# LEDprotoFix.net
KiCad netlist of a schematic drawn in EAGLE
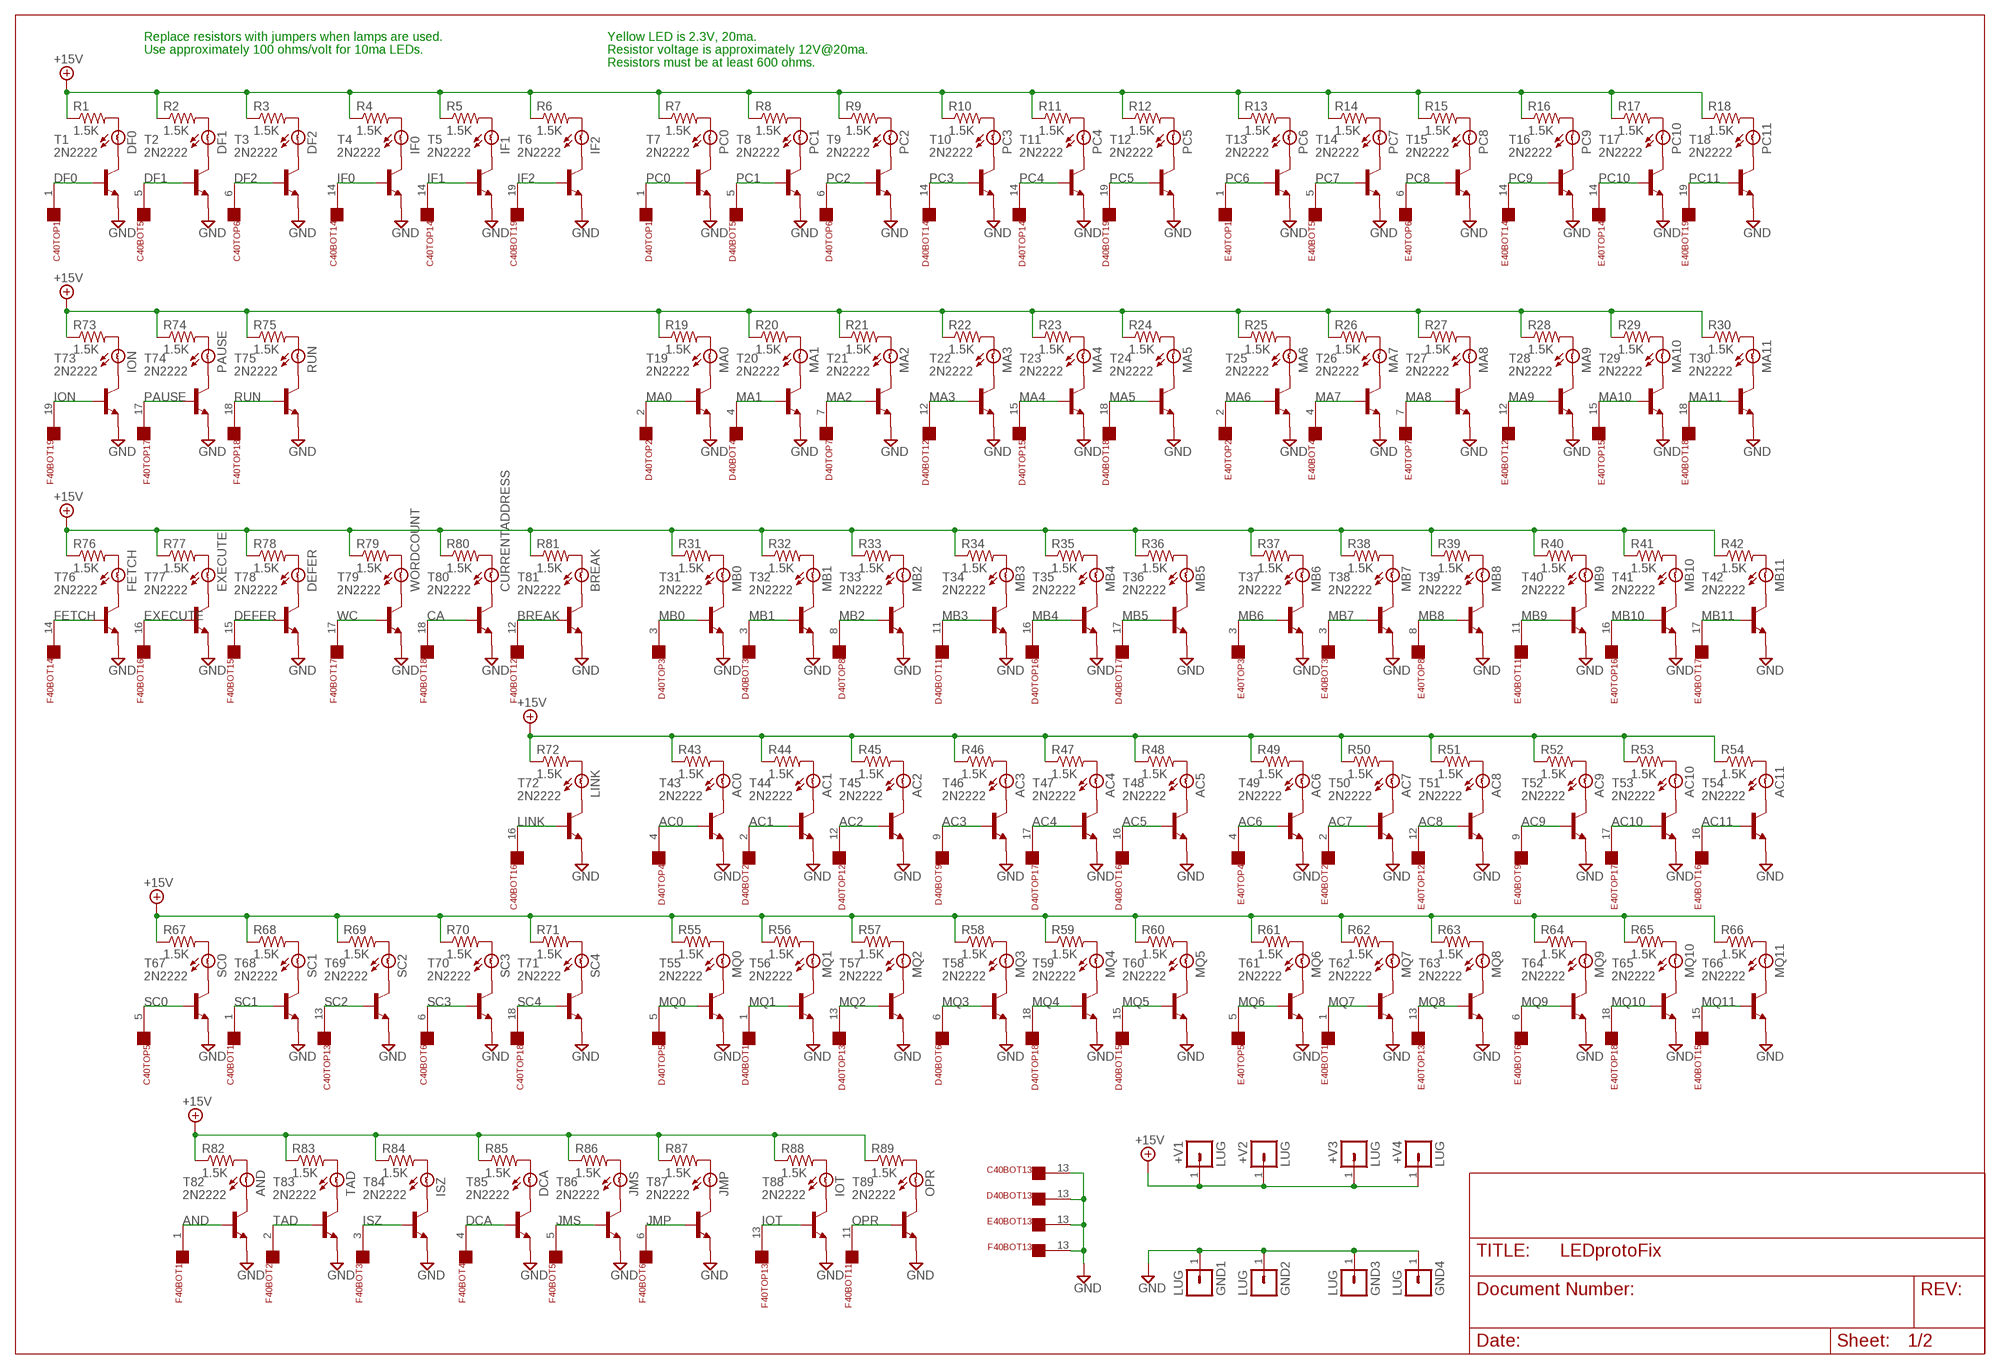
[diagram p0: schematic, sheet 1]
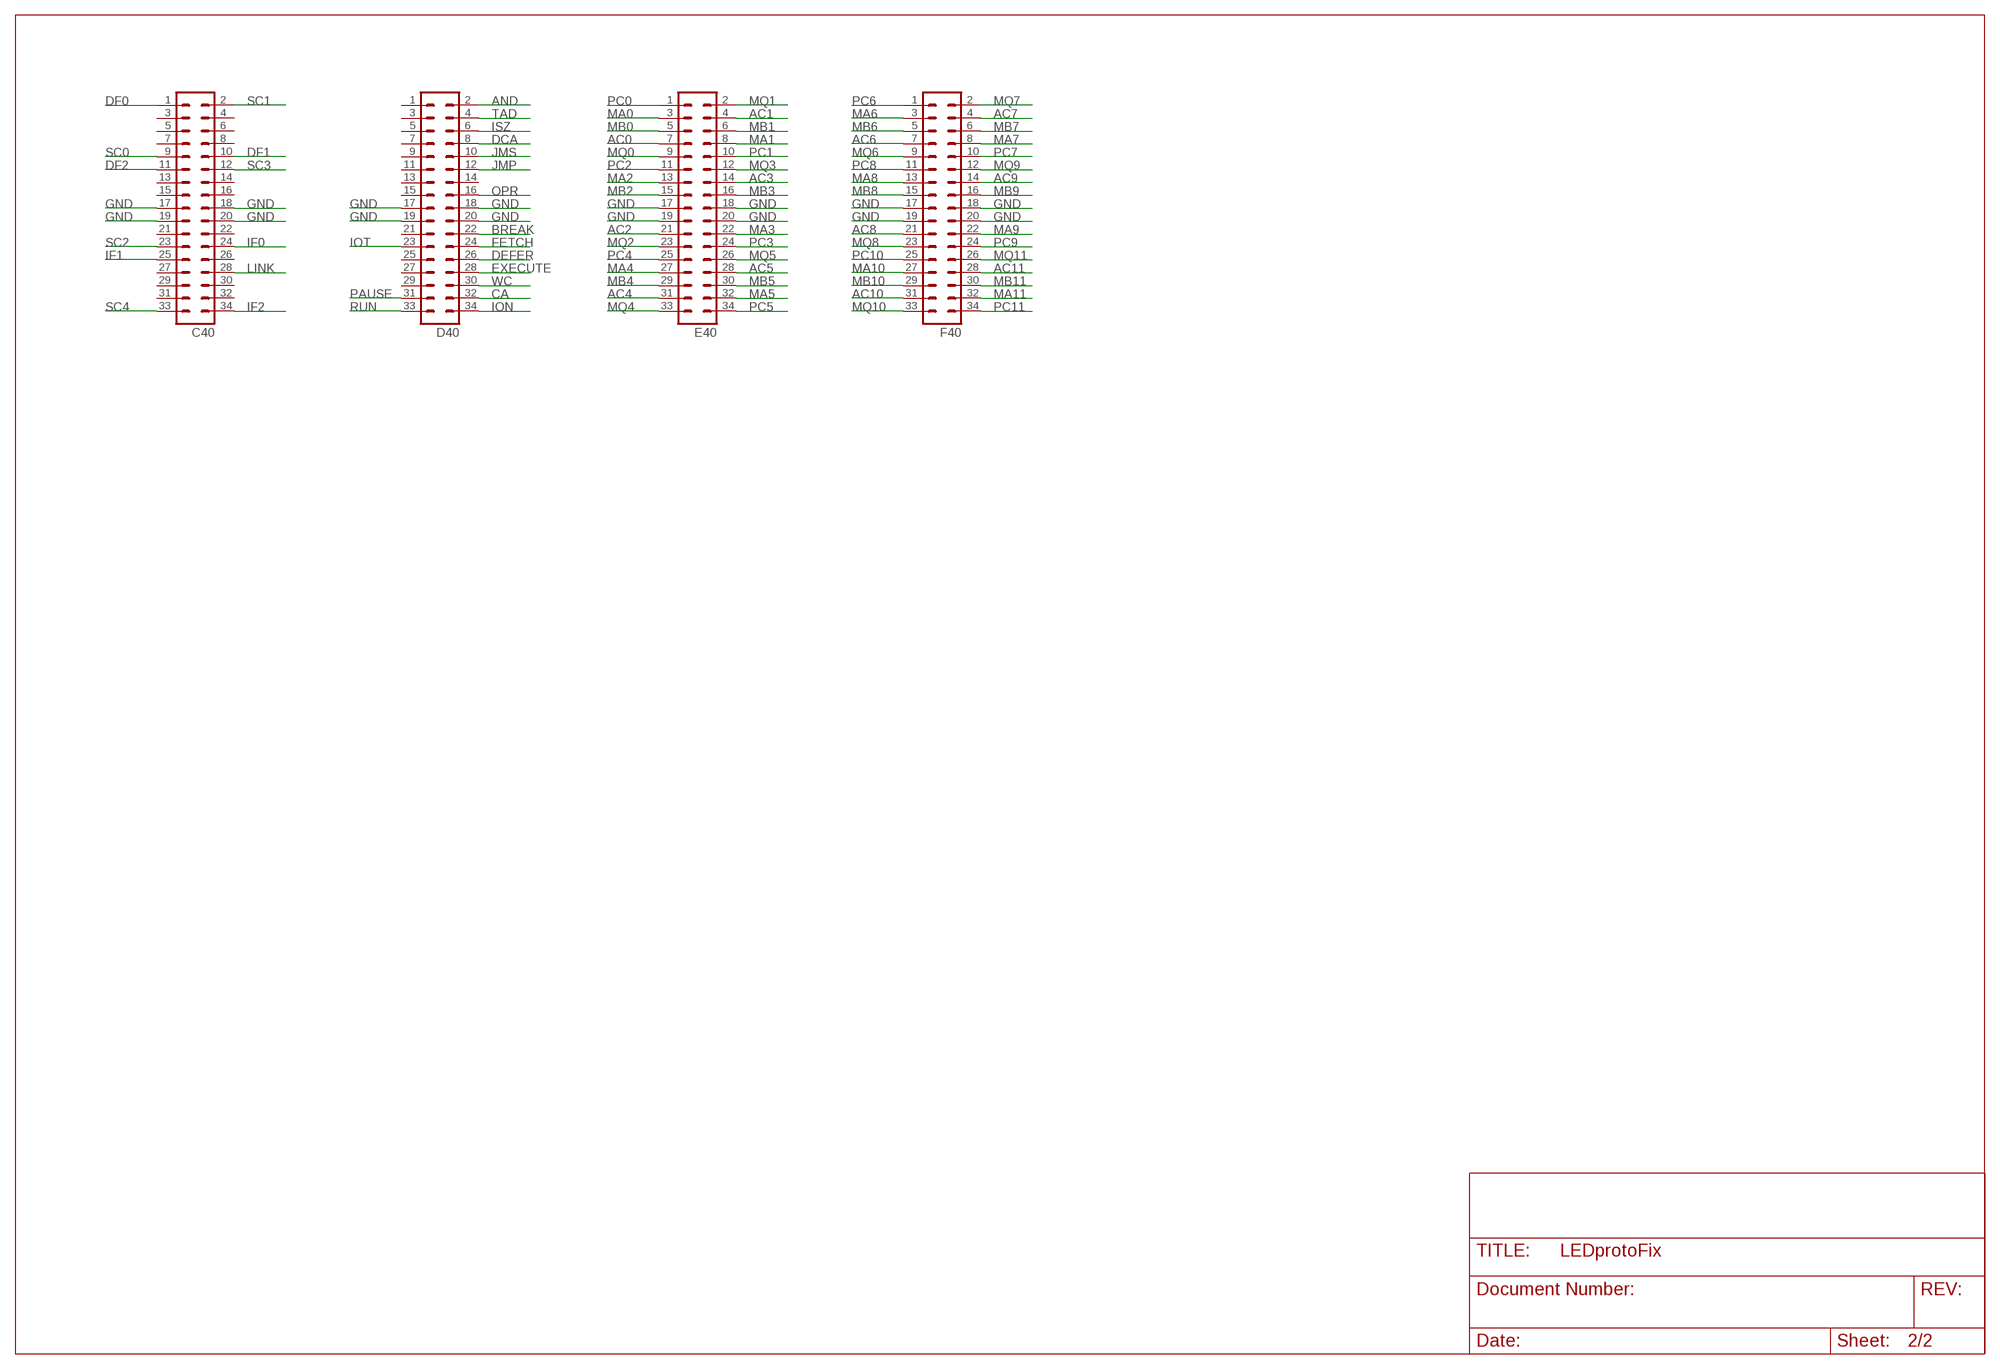
[diagram p1: schematic, sheet 2]

(export (version "E")
  (design (tool "Eeschema 10.0.6"))
  (components
    (comp (ref "+V1")
      (value "LUG")
      (footprint "eagle-import:SPADELUG")
      (libsource (lib "eagle-import") (part "LUG"))
    )
    (comp (ref "+V2")
      (value "LUG")
      (footprint "eagle-import:SPADELUG")
      (libsource (lib "eagle-import") (part "LUG"))
    )
    (comp (ref "+V3")
      (value "LUG")
      (footprint "eagle-import:SPADELUG")
      (libsource (lib "eagle-import") (part "LUG"))
    )
    (comp (ref "+V4")
      (value "LUG")
      (footprint "eagle-import:SPADELUG")
      (libsource (lib "eagle-import") (part "LUG"))
    )
    (comp (ref "AC0")
      (value "BULB")
      (footprint "eagle-import:BULB")
      (libsource (lib "eagle-import") (part "BULB"))
    )
    (comp (ref "AC1")
      (value "BULB")
      (footprint "eagle-import:BULB")
      (libsource (lib "eagle-import") (part "BULB"))
    )
    (comp (ref "AC2")
      (value "BULB")
      (footprint "eagle-import:BULB")
      (libsource (lib "eagle-import") (part "BULB"))
    )
    (comp (ref "AC3")
      (value "BULB")
      (footprint "eagle-import:BULB")
      (libsource (lib "eagle-import") (part "BULB"))
    )
    (comp (ref "AC4")
      (value "BULB")
      (footprint "eagle-import:BULB")
      (libsource (lib "eagle-import") (part "BULB"))
    )
    (comp (ref "AC5")
      (value "BULB")
      (footprint "eagle-import:BULB")
      (libsource (lib "eagle-import") (part "BULB"))
    )
    (comp (ref "AC6")
      (value "BULB")
      (footprint "eagle-import:BULB")
      (libsource (lib "eagle-import") (part "BULB"))
    )
    (comp (ref "AC7")
      (value "BULB")
      (footprint "eagle-import:BULB")
      (libsource (lib "eagle-import") (part "BULB"))
    )
    (comp (ref "AC8")
      (value "BULB")
      (footprint "eagle-import:BULB")
      (libsource (lib "eagle-import") (part "BULB"))
    )
    (comp (ref "AC9")
      (value "BULB")
      (footprint "eagle-import:BULB")
      (libsource (lib "eagle-import") (part "BULB"))
    )
    (comp (ref "AC10")
      (value "BULB")
      (footprint "eagle-import:BULB")
      (libsource (lib "eagle-import") (part "BULB"))
    )
    (comp (ref "AC11")
      (value "BULB")
      (footprint "eagle-import:BULB")
      (libsource (lib "eagle-import") (part "BULB"))
    )
    (comp (ref "AND")
      (value "BULB")
      (footprint "eagle-import:BULB")
      (libsource (lib "eagle-import") (part "BULB"))
    )
    (comp (ref "BREAK")
      (value "BULB")
      (footprint "eagle-import:BULB")
      (libsource (lib "eagle-import") (part "BULB"))
    )
    (comp (ref "C40BOT")
      (value "FLEX19")
      (footprint "eagle-import:FLEX19")
      (libsource (lib "eagle-import") (part "FLEX19"))
    )
    (comp (ref "C40TOP")
      (value "FLEX19")
      (footprint "eagle-import:FLEX19")
      (libsource (lib "eagle-import") (part "FLEX19"))
    )
    (comp (ref "CURRENTADDRESS")
      (value "BULB")
      (footprint "eagle-import:BULB")
      (libsource (lib "eagle-import") (part "BULB"))
    )
    (comp (ref "D40BOT")
      (value "FLEX19")
      (footprint "eagle-import:FLEX19")
      (libsource (lib "eagle-import") (part "FLEX19"))
    )
    (comp (ref "D40TOP")
      (value "FLEX19")
      (footprint "eagle-import:FLEX19")
      (libsource (lib "eagle-import") (part "FLEX19"))
    )
    (comp (ref "DCA")
      (value "BULB")
      (footprint "eagle-import:BULB")
      (libsource (lib "eagle-import") (part "BULB"))
    )
    (comp (ref "DEFER")
      (value "BULB")
      (footprint "eagle-import:BULB")
      (libsource (lib "eagle-import") (part "BULB"))
    )
    (comp (ref "DF0")
      (value "BULB")
      (footprint "eagle-import:BULB")
      (libsource (lib "eagle-import") (part "BULB"))
    )
    (comp (ref "DF1")
      (value "BULB")
      (footprint "eagle-import:BULB")
      (libsource (lib "eagle-import") (part "BULB"))
    )
    (comp (ref "DF2")
      (value "BULB")
      (footprint "eagle-import:BULB")
      (libsource (lib "eagle-import") (part "BULB"))
    )
    (comp (ref "E40BOT")
      (value "FLEX19")
      (footprint "eagle-import:FLEX19")
      (libsource (lib "eagle-import") (part "FLEX19"))
    )
    (comp (ref "E40TOP")
      (value "FLEX19")
      (footprint "eagle-import:FLEX19")
      (libsource (lib "eagle-import") (part "FLEX19"))
    )
    (comp (ref "EXECUTE")
      (value "BULB")
      (footprint "eagle-import:BULB")
      (libsource (lib "eagle-import") (part "BULB"))
    )
    (comp (ref "F40BOT")
      (value "FLEX19")
      (footprint "eagle-import:FLEX19")
      (libsource (lib "eagle-import") (part "FLEX19"))
    )
    (comp (ref "F40TOP")
      (value "FLEX19")
      (footprint "eagle-import:FLEX19")
      (libsource (lib "eagle-import") (part "FLEX19"))
    )
    (comp (ref "FETCH")
      (value "BULB")
      (footprint "eagle-import:BULB")
      (libsource (lib "eagle-import") (part "BULB"))
    )
    (comp (ref "GND1")
      (value "LUG")
      (footprint "eagle-import:SPADELUG")
      (libsource (lib "eagle-import") (part "LUG"))
    )
    (comp (ref "GND2")
      (value "LUG")
      (footprint "eagle-import:SPADELUG")
      (libsource (lib "eagle-import") (part "LUG"))
    )
    (comp (ref "GND3")
      (value "LUG")
      (footprint "eagle-import:SPADELUG")
      (libsource (lib "eagle-import") (part "LUG"))
    )
    (comp (ref "GND4")
      (value "LUG")
      (footprint "eagle-import:SPADELUG")
      (libsource (lib "eagle-import") (part "LUG"))
    )
    (comp (ref "IF0")
      (value "BULB")
      (footprint "eagle-import:BULB")
      (libsource (lib "eagle-import") (part "BULB"))
    )
    (comp (ref "IF1")
      (value "BULB")
      (footprint "eagle-import:BULB")
      (libsource (lib "eagle-import") (part "BULB"))
    )
    (comp (ref "IF2")
      (value "BULB")
      (footprint "eagle-import:BULB")
      (libsource (lib "eagle-import") (part "BULB"))
    )
    (comp (ref "ION")
      (value "BULB")
      (footprint "eagle-import:BULB")
      (libsource (lib "eagle-import") (part "BULB"))
    )
    (comp (ref "IOT")
      (value "BULB")
      (footprint "eagle-import:BULB")
      (libsource (lib "eagle-import") (part "BULB"))
    )
    (comp (ref "ISZ")
      (value "BULB")
      (footprint "eagle-import:BULB")
      (libsource (lib "eagle-import") (part "BULB"))
    )
    (comp (ref "JMP")
      (value "BULB")
      (footprint "eagle-import:BULB")
      (libsource (lib "eagle-import") (part "BULB"))
    )
    (comp (ref "JMS")
      (value "BULB")
      (footprint "eagle-import:BULB")
      (libsource (lib "eagle-import") (part "BULB"))
    )
    (comp (ref "LINK")
      (value "BULB")
      (footprint "eagle-import:BULB")
      (libsource (lib "eagle-import") (part "BULB"))
    )
    (comp (ref "MA0")
      (value "BULB")
      (footprint "eagle-import:BULB")
      (libsource (lib "eagle-import") (part "BULB"))
    )
    (comp (ref "MA1")
      (value "BULB")
      (footprint "eagle-import:BULB")
      (libsource (lib "eagle-import") (part "BULB"))
    )
    (comp (ref "MA2")
      (value "BULB")
      (footprint "eagle-import:BULB")
      (libsource (lib "eagle-import") (part "BULB"))
    )
    (comp (ref "MA3")
      (value "BULB")
      (footprint "eagle-import:BULB")
      (libsource (lib "eagle-import") (part "BULB"))
    )
    (comp (ref "MA4")
      (value "BULB")
      (footprint "eagle-import:BULB")
      (libsource (lib "eagle-import") (part "BULB"))
    )
    (comp (ref "MA5")
      (value "BULB")
      (footprint "eagle-import:BULB")
      (libsource (lib "eagle-import") (part "BULB"))
    )
    (comp (ref "MA6")
      (value "BULB")
      (footprint "eagle-import:BULB")
      (libsource (lib "eagle-import") (part "BULB"))
    )
    (comp (ref "MA7")
      (value "BULB")
      (footprint "eagle-import:BULB")
      (libsource (lib "eagle-import") (part "BULB"))
    )
    (comp (ref "MA8")
      (value "BULB")
      (footprint "eagle-import:BULB")
      (libsource (lib "eagle-import") (part "BULB"))
    )
    (comp (ref "MA9")
      (value "BULB")
      (footprint "eagle-import:BULB")
      (libsource (lib "eagle-import") (part "BULB"))
    )
    (comp (ref "MA10")
      (value "BULB")
      (footprint "eagle-import:BULB")
      (libsource (lib "eagle-import") (part "BULB"))
    )
    (comp (ref "MA11")
      (value "BULB")
      (footprint "eagle-import:BULB")
      (libsource (lib "eagle-import") (part "BULB"))
    )
    (comp (ref "MB0")
      (value "BULB")
      (footprint "eagle-import:BULB")
      (libsource (lib "eagle-import") (part "BULB"))
    )
    (comp (ref "MB1")
      (value "BULB")
      (footprint "eagle-import:BULB")
      (libsource (lib "eagle-import") (part "BULB"))
    )
    (comp (ref "MB2")
      (value "BULB")
      (footprint "eagle-import:BULB")
      (libsource (lib "eagle-import") (part "BULB"))
    )
    (comp (ref "MB3")
      (value "BULB")
      (footprint "eagle-import:BULB")
      (libsource (lib "eagle-import") (part "BULB"))
    )
    (comp (ref "MB4")
      (value "BULB")
      (footprint "eagle-import:BULB")
      (libsource (lib "eagle-import") (part "BULB"))
    )
    (comp (ref "MB5")
      (value "BULB")
      (footprint "eagle-import:BULB")
      (libsource (lib "eagle-import") (part "BULB"))
    )
    (comp (ref "MB6")
      (value "BULB")
      (footprint "eagle-import:BULB")
      (libsource (lib "eagle-import") (part "BULB"))
    )
    (comp (ref "MB7")
      (value "BULB")
      (footprint "eagle-import:BULB")
      (libsource (lib "eagle-import") (part "BULB"))
    )
    (comp (ref "MB8")
      (value "BULB")
      (footprint "eagle-import:BULB")
      (libsource (lib "eagle-import") (part "BULB"))
    )
    (comp (ref "MB9")
      (value "BULB")
      (footprint "eagle-import:BULB")
      (libsource (lib "eagle-import") (part "BULB"))
    )
    (comp (ref "MB10")
      (value "BULB")
      (footprint "eagle-import:BULB")
      (libsource (lib "eagle-import") (part "BULB"))
    )
    (comp (ref "MB11")
      (value "BULB")
      (footprint "eagle-import:BULB")
      (libsource (lib "eagle-import") (part "BULB"))
    )
    (comp (ref "MQ0")
      (value "BULB")
      (footprint "eagle-import:BULB")
      (libsource (lib "eagle-import") (part "BULB"))
    )
    (comp (ref "MQ1")
      (value "BULB")
      (footprint "eagle-import:BULB")
      (libsource (lib "eagle-import") (part "BULB"))
    )
    (comp (ref "MQ2")
      (value "BULB")
      (footprint "eagle-import:BULB")
      (libsource (lib "eagle-import") (part "BULB"))
    )
    (comp (ref "MQ3")
      (value "BULB")
      (footprint "eagle-import:BULB")
      (libsource (lib "eagle-import") (part "BULB"))
    )
    (comp (ref "MQ4")
      (value "BULB")
      (footprint "eagle-import:BULB")
      (libsource (lib "eagle-import") (part "BULB"))
    )
    (comp (ref "MQ5")
      (value "BULB")
      (footprint "eagle-import:BULB")
      (libsource (lib "eagle-import") (part "BULB"))
    )
    (comp (ref "MQ6")
      (value "BULB")
      (footprint "eagle-import:BULB")
      (libsource (lib "eagle-import") (part "BULB"))
    )
    (comp (ref "MQ7")
      (value "BULB")
      (footprint "eagle-import:BULB")
      (libsource (lib "eagle-import") (part "BULB"))
    )
    (comp (ref "MQ8")
      (value "BULB")
      (footprint "eagle-import:BULB")
      (libsource (lib "eagle-import") (part "BULB"))
    )
    (comp (ref "MQ9")
      (value "BULB")
      (footprint "eagle-import:BULB")
      (libsource (lib "eagle-import") (part "BULB"))
    )
    (comp (ref "MQ10")
      (value "BULB")
      (footprint "eagle-import:BULB")
      (libsource (lib "eagle-import") (part "BULB"))
    )
    (comp (ref "MQ11")
      (value "BULB")
      (footprint "eagle-import:BULB")
      (libsource (lib "eagle-import") (part "BULB"))
    )
    (comp (ref "OPR")
      (value "BULB")
      (footprint "eagle-import:BULB")
      (libsource (lib "eagle-import") (part "BULB"))
    )
    (comp (ref "PAUSE")
      (value "BULB")
      (footprint "eagle-import:BULB")
      (libsource (lib "eagle-import") (part "BULB"))
    )
    (comp (ref "PC0")
      (value "BULB")
      (footprint "eagle-import:BULB")
      (libsource (lib "eagle-import") (part "BULB"))
    )
    (comp (ref "PC1")
      (value "BULB")
      (footprint "eagle-import:BULB")
      (libsource (lib "eagle-import") (part "BULB"))
    )
    (comp (ref "PC2")
      (value "BULB")
      (footprint "eagle-import:BULB")
      (libsource (lib "eagle-import") (part "BULB"))
    )
    (comp (ref "PC3")
      (value "BULB")
      (footprint "eagle-import:BULB")
      (libsource (lib "eagle-import") (part "BULB"))
    )
    (comp (ref "PC4")
      (value "BULB")
      (footprint "eagle-import:BULB")
      (libsource (lib "eagle-import") (part "BULB"))
    )
    (comp (ref "PC5")
      (value "BULB")
      (footprint "eagle-import:BULB")
      (libsource (lib "eagle-import") (part "BULB"))
    )
    (comp (ref "PC6")
      (value "BULB")
      (footprint "eagle-import:BULB")
      (libsource (lib "eagle-import") (part "BULB"))
    )
    (comp (ref "PC7")
      (value "BULB")
      (footprint "eagle-import:BULB")
      (libsource (lib "eagle-import") (part "BULB"))
    )
    (comp (ref "PC8")
      (value "BULB")
      (footprint "eagle-import:BULB")
      (libsource (lib "eagle-import") (part "BULB"))
    )
    (comp (ref "PC9")
      (value "BULB")
      (footprint "eagle-import:BULB")
      (libsource (lib "eagle-import") (part "BULB"))
    )
    (comp (ref "PC10")
      (value "BULB")
      (footprint "eagle-import:BULB")
      (libsource (lib "eagle-import") (part "BULB"))
    )
    (comp (ref "PC11")
      (value "BULB")
      (footprint "eagle-import:BULB")
      (libsource (lib "eagle-import") (part "BULB"))
    )
    (comp (ref "R1")
      (value "1.5K")
      (footprint "eagle-import:0207_10")
      (libsource (lib "eagle-import") (part "R-US_0207/10"))
    )
    (comp (ref "R2")
      (value "1.5K")
      (footprint "eagle-import:0207_10")
      (libsource (lib "eagle-import") (part "R-US_0207/10"))
    )
    (comp (ref "R3")
      (value "1.5K")
      (footprint "eagle-import:0207_10")
      (libsource (lib "eagle-import") (part "R-US_0207/10"))
    )
    (comp (ref "R4")
      (value "1.5K")
      (footprint "eagle-import:0207_10")
      (libsource (lib "eagle-import") (part "R-US_0207/10"))
    )
    (comp (ref "R5")
      (value "1.5K")
      (footprint "eagle-import:0207_10")
      (libsource (lib "eagle-import") (part "R-US_0207/10"))
    )
    (comp (ref "R6")
      (value "1.5K")
      (footprint "eagle-import:0207_10")
      (libsource (lib "eagle-import") (part "R-US_0207/10"))
    )
    (comp (ref "R7")
      (value "1.5K")
      (footprint "eagle-import:0207_10")
      (libsource (lib "eagle-import") (part "R-US_0207/10"))
    )
    (comp (ref "R8")
      (value "1.5K")
      (footprint "eagle-import:0207_10")
      (libsource (lib "eagle-import") (part "R-US_0207/10"))
    )
    (comp (ref "R9")
      (value "1.5K")
      (footprint "eagle-import:0207_10")
      (libsource (lib "eagle-import") (part "R-US_0207/10"))
    )
    (comp (ref "R10")
      (value "1.5K")
      (footprint "eagle-import:0207_10")
      (libsource (lib "eagle-import") (part "R-US_0207/10"))
    )
    (comp (ref "R11")
      (value "1.5K")
      (footprint "eagle-import:0207_10")
      (libsource (lib "eagle-import") (part "R-US_0207/10"))
    )
    (comp (ref "R12")
      (value "1.5K")
      (footprint "eagle-import:0207_10")
      (libsource (lib "eagle-import") (part "R-US_0207/10"))
    )
    (comp (ref "R13")
      (value "1.5K")
      (footprint "eagle-import:0207_10")
      (libsource (lib "eagle-import") (part "R-US_0207/10"))
    )
    (comp (ref "R14")
      (value "1.5K")
      (footprint "eagle-import:0207_10")
      (libsource (lib "eagle-import") (part "R-US_0207/10"))
    )
    (comp (ref "R15")
      (value "1.5K")
      (footprint "eagle-import:0207_10")
      (libsource (lib "eagle-import") (part "R-US_0207/10"))
    )
    (comp (ref "R16")
      (value "1.5K")
      (footprint "eagle-import:0207_10")
      (libsource (lib "eagle-import") (part "R-US_0207/10"))
    )
    (comp (ref "R17")
      (value "1.5K")
      (footprint "eagle-import:0207_10")
      (libsource (lib "eagle-import") (part "R-US_0207/10"))
    )
    (comp (ref "R18")
      (value "1.5K")
      (footprint "eagle-import:0207_10")
      (libsource (lib "eagle-import") (part "R-US_0207/10"))
    )
    (comp (ref "R19")
      (value "1.5K")
      (footprint "eagle-import:0207_10")
      (libsource (lib "eagle-import") (part "R-US_0207/10"))
    )
    (comp (ref "R20")
      (value "1.5K")
      (footprint "eagle-import:0207_10")
      (libsource (lib "eagle-import") (part "R-US_0207/10"))
    )
    (comp (ref "R21")
      (value "1.5K")
      (footprint "eagle-import:0207_10")
      (libsource (lib "eagle-import") (part "R-US_0207/10"))
    )
    (comp (ref "R22")
      (value "1.5K")
      (footprint "eagle-import:0207_10")
      (libsource (lib "eagle-import") (part "R-US_0207/10"))
    )
    (comp (ref "R23")
      (value "1.5K")
      (footprint "eagle-import:0207_10")
      (libsource (lib "eagle-import") (part "R-US_0207/10"))
    )
    (comp (ref "R24")
      (value "1.5K")
      (footprint "eagle-import:0207_10")
      (libsource (lib "eagle-import") (part "R-US_0207/10"))
    )
    (comp (ref "R25")
      (value "1.5K")
      (footprint "eagle-import:0207_10")
      (libsource (lib "eagle-import") (part "R-US_0207/10"))
    )
    (comp (ref "R26")
      (value "1.5K")
      (footprint "eagle-import:0207_10")
      (libsource (lib "eagle-import") (part "R-US_0207/10"))
    )
    (comp (ref "R27")
      (value "1.5K")
      (footprint "eagle-import:0207_10")
      (libsource (lib "eagle-import") (part "R-US_0207/10"))
    )
    (comp (ref "R28")
      (value "1.5K")
      (footprint "eagle-import:0207_10")
      (libsource (lib "eagle-import") (part "R-US_0207/10"))
    )
    (comp (ref "R29")
      (value "1.5K")
      (footprint "eagle-import:0207_10")
      (libsource (lib "eagle-import") (part "R-US_0207/10"))
    )
    (comp (ref "R30")
      (value "1.5K")
      (footprint "eagle-import:0207_10")
      (libsource (lib "eagle-import") (part "R-US_0207/10"))
    )
    (comp (ref "R31")
      (value "1.5K")
      (footprint "eagle-import:0207_10")
      (libsource (lib "eagle-import") (part "R-US_0207/10"))
    )
    (comp (ref "R32")
      (value "1.5K")
      (footprint "eagle-import:0207_10")
      (libsource (lib "eagle-import") (part "R-US_0207/10"))
    )
    (comp (ref "R33")
      (value "1.5K")
      (footprint "eagle-import:0207_10")
      (libsource (lib "eagle-import") (part "R-US_0207/10"))
    )
    (comp (ref "R34")
      (value "1.5K")
      (footprint "eagle-import:0207_10")
      (libsource (lib "eagle-import") (part "R-US_0207/10"))
    )
    (comp (ref "R35")
      (value "1.5K")
      (footprint "eagle-import:0207_10")
      (libsource (lib "eagle-import") (part "R-US_0207/10"))
    )
    (comp (ref "R36")
      (value "1.5K")
      (footprint "eagle-import:0207_10")
      (libsource (lib "eagle-import") (part "R-US_0207/10"))
    )
    (comp (ref "R37")
      (value "1.5K")
      (footprint "eagle-import:0207_10")
      (libsource (lib "eagle-import") (part "R-US_0207/10"))
    )
    (comp (ref "R38")
      (value "1.5K")
      (footprint "eagle-import:0207_10")
      (libsource (lib "eagle-import") (part "R-US_0207/10"))
    )
    (comp (ref "R39")
      (value "1.5K")
      (footprint "eagle-import:0207_10")
      (libsource (lib "eagle-import") (part "R-US_0207/10"))
    )
    (comp (ref "R40")
      (value "1.5K")
      (footprint "eagle-import:0207_10")
      (libsource (lib "eagle-import") (part "R-US_0207/10"))
    )
    (comp (ref "R41")
      (value "1.5K")
      (footprint "eagle-import:0207_10")
      (libsource (lib "eagle-import") (part "R-US_0207/10"))
    )
    (comp (ref "R42")
      (value "1.5K")
      (footprint "eagle-import:0207_10")
      (libsource (lib "eagle-import") (part "R-US_0207/10"))
    )
    (comp (ref "R43")
      (value "1.5K")
      (footprint "eagle-import:0207_10")
      (libsource (lib "eagle-import") (part "R-US_0207/10"))
    )
    (comp (ref "R44")
      (value "1.5K")
      (footprint "eagle-import:0207_10")
      (libsource (lib "eagle-import") (part "R-US_0207/10"))
    )
    (comp (ref "R45")
      (value "1.5K")
      (footprint "eagle-import:0207_10")
      (libsource (lib "eagle-import") (part "R-US_0207/10"))
    )
    (comp (ref "R46")
      (value "1.5K")
      (footprint "eagle-import:0207_10")
      (libsource (lib "eagle-import") (part "R-US_0207/10"))
    )
    (comp (ref "R47")
      (value "1.5K")
      (footprint "eagle-import:0207_10")
      (libsource (lib "eagle-import") (part "R-US_0207/10"))
    )
    (comp (ref "R48")
      (value "1.5K")
      (footprint "eagle-import:0207_10")
      (libsource (lib "eagle-import") (part "R-US_0207/10"))
    )
    (comp (ref "R49")
      (value "1.5K")
      (footprint "eagle-import:0207_10")
      (libsource (lib "eagle-import") (part "R-US_0207/10"))
    )
    (comp (ref "R50")
      (value "1.5K")
      (footprint "eagle-import:0207_10")
      (libsource (lib "eagle-import") (part "R-US_0207/10"))
    )
    (comp (ref "R51")
      (value "1.5K")
      (footprint "eagle-import:0207_10")
      (libsource (lib "eagle-import") (part "R-US_0207/10"))
    )
    (comp (ref "R52")
      (value "1.5K")
      (footprint "eagle-import:0207_10")
      (libsource (lib "eagle-import") (part "R-US_0207/10"))
    )
    (comp (ref "R53")
      (value "1.5K")
      (footprint "eagle-import:0207_10")
      (libsource (lib "eagle-import") (part "R-US_0207/10"))
    )
    (comp (ref "R54")
      (value "1.5K")
      (footprint "eagle-import:0207_10")
      (libsource (lib "eagle-import") (part "R-US_0207/10"))
    )
    (comp (ref "R55")
      (value "1.5K")
      (footprint "eagle-import:0207_10")
      (libsource (lib "eagle-import") (part "R-US_0207/10"))
    )
    (comp (ref "R56")
      (value "1.5K")
      (footprint "eagle-import:0207_10")
      (libsource (lib "eagle-import") (part "R-US_0207/10"))
    )
    (comp (ref "R57")
      (value "1.5K")
      (footprint "eagle-import:0207_10")
      (libsource (lib "eagle-import") (part "R-US_0207/10"))
    )
    (comp (ref "R58")
      (value "1.5K")
      (footprint "eagle-import:0207_10")
      (libsource (lib "eagle-import") (part "R-US_0207/10"))
    )
    (comp (ref "R59")
      (value "1.5K")
      (footprint "eagle-import:0207_10")
      (libsource (lib "eagle-import") (part "R-US_0207/10"))
    )
    (comp (ref "R60")
      (value "1.5K")
      (footprint "eagle-import:0207_10")
      (libsource (lib "eagle-import") (part "R-US_0207/10"))
    )
    (comp (ref "R61")
      (value "1.5K")
      (footprint "eagle-import:0207_10")
      (libsource (lib "eagle-import") (part "R-US_0207/10"))
    )
    (comp (ref "R62")
      (value "1.5K")
      (footprint "eagle-import:0207_10")
      (libsource (lib "eagle-import") (part "R-US_0207/10"))
    )
    (comp (ref "R63")
      (value "1.5K")
      (footprint "eagle-import:0207_10")
      (libsource (lib "eagle-import") (part "R-US_0207/10"))
    )
    (comp (ref "R64")
      (value "1.5K")
      (footprint "eagle-import:0207_10")
      (libsource (lib "eagle-import") (part "R-US_0207/10"))
    )
    (comp (ref "R65")
      (value "1.5K")
      (footprint "eagle-import:0207_10")
      (libsource (lib "eagle-import") (part "R-US_0207/10"))
    )
    (comp (ref "R66")
      (value "1.5K")
      (footprint "eagle-import:0207_10")
      (libsource (lib "eagle-import") (part "R-US_0207/10"))
    )
    (comp (ref "R67")
      (value "1.5K")
      (footprint "eagle-import:0207_10")
      (libsource (lib "eagle-import") (part "R-US_0207/10"))
    )
    (comp (ref "R68")
      (value "1.5K")
      (footprint "eagle-import:0207_10")
      (libsource (lib "eagle-import") (part "R-US_0207/10"))
    )
    (comp (ref "R69")
      (value "1.5K")
      (footprint "eagle-import:0207_10")
      (libsource (lib "eagle-import") (part "R-US_0207/10"))
    )
    (comp (ref "R70")
      (value "1.5K")
      (footprint "eagle-import:0207_10")
      (libsource (lib "eagle-import") (part "R-US_0207/10"))
    )
    (comp (ref "R71")
      (value "1.5K")
      (footprint "eagle-import:0207_10")
      (libsource (lib "eagle-import") (part "R-US_0207/10"))
    )
    (comp (ref "R72")
      (value "1.5K")
      (footprint "eagle-import:0207_10")
      (libsource (lib "eagle-import") (part "R-US_0207/10"))
    )
    (comp (ref "R73")
      (value "1.5K")
      (footprint "eagle-import:0207_10")
      (libsource (lib "eagle-import") (part "R-US_0207/10"))
    )
    (comp (ref "R74")
      (value "1.5K")
      (footprint "eagle-import:0207_10")
      (libsource (lib "eagle-import") (part "R-US_0207/10"))
    )
    (comp (ref "R75")
      (value "1.5K")
      (footprint "eagle-import:0207_10")
      (libsource (lib "eagle-import") (part "R-US_0207/10"))
    )
    (comp (ref "R76")
      (value "1.5K")
      (footprint "eagle-import:0207_10")
      (libsource (lib "eagle-import") (part "R-US_0207/10"))
    )
    (comp (ref "R77")
      (value "1.5K")
      (footprint "eagle-import:0207_10")
      (libsource (lib "eagle-import") (part "R-US_0207/10"))
    )
    (comp (ref "R78")
      (value "1.5K")
      (footprint "eagle-import:0207_10")
      (libsource (lib "eagle-import") (part "R-US_0207/10"))
    )
    (comp (ref "R79")
      (value "1.5K")
      (footprint "eagle-import:0207_10")
      (libsource (lib "eagle-import") (part "R-US_0207/10"))
    )
    (comp (ref "R80")
      (value "1.5K")
      (footprint "eagle-import:0207_10")
      (libsource (lib "eagle-import") (part "R-US_0207/10"))
    )
    (comp (ref "R81")
      (value "1.5K")
      (footprint "eagle-import:0207_10")
      (libsource (lib "eagle-import") (part "R-US_0207/10"))
    )
    (comp (ref "R82")
      (value "1.5K")
      (footprint "eagle-import:0207_10")
      (libsource (lib "eagle-import") (part "R-US_0207/10"))
    )
    (comp (ref "R83")
      (value "1.5K")
      (footprint "eagle-import:0207_10")
      (libsource (lib "eagle-import") (part "R-US_0207/10"))
    )
    (comp (ref "R84")
      (value "1.5K")
      (footprint "eagle-import:0207_10")
      (libsource (lib "eagle-import") (part "R-US_0207/10"))
    )
    (comp (ref "R85")
      (value "1.5K")
      (footprint "eagle-import:0207_10")
      (libsource (lib "eagle-import") (part "R-US_0207/10"))
    )
    (comp (ref "R86")
      (value "1.5K")
      (footprint "eagle-import:0207_10")
      (libsource (lib "eagle-import") (part "R-US_0207/10"))
    )
    (comp (ref "R87")
      (value "1.5K")
      (footprint "eagle-import:0207_10")
      (libsource (lib "eagle-import") (part "R-US_0207/10"))
    )
    (comp (ref "R88")
      (value "1.5K")
      (footprint "eagle-import:0207_10")
      (libsource (lib "eagle-import") (part "R-US_0207/10"))
    )
    (comp (ref "R89")
      (value "1.5K")
      (footprint "eagle-import:0207_10")
      (libsource (lib "eagle-import") (part "R-US_0207/10"))
    )
    (comp (ref "RUN")
      (value "BULB")
      (footprint "eagle-import:BULB")
      (libsource (lib "eagle-import") (part "BULB"))
    )
    (comp (ref "SC0")
      (value "BULB")
      (footprint "eagle-import:BULB")
      (libsource (lib "eagle-import") (part "BULB"))
    )
    (comp (ref "SC1")
      (value "BULB")
      (footprint "eagle-import:BULB")
      (libsource (lib "eagle-import") (part "BULB"))
    )
    (comp (ref "SC2")
      (value "BULB")
      (footprint "eagle-import:BULB")
      (libsource (lib "eagle-import") (part "BULB"))
    )
    (comp (ref "SC3")
      (value "BULB")
      (footprint "eagle-import:BULB")
      (libsource (lib "eagle-import") (part "BULB"))
    )
    (comp (ref "SC4")
      (value "BULB")
      (footprint "eagle-import:BULB")
      (libsource (lib "eagle-import") (part "BULB"))
    )
    (comp (ref "T1")
      (value "2N2222")
      (footprint "eagle-import:TO92")
      (libsource (lib "eagle-import") (part "-NPN-TO92"))
    )
    (comp (ref "T2")
      (value "2N2222")
      (footprint "eagle-import:TO92")
      (libsource (lib "eagle-import") (part "-NPN-TO92"))
    )
    (comp (ref "T3")
      (value "2N2222")
      (footprint "eagle-import:TO92")
      (libsource (lib "eagle-import") (part "-NPN-TO92"))
    )
    (comp (ref "T4")
      (value "2N2222")
      (footprint "eagle-import:TO92")
      (libsource (lib "eagle-import") (part "-NPN-TO92"))
    )
    (comp (ref "T5")
      (value "2N2222")
      (footprint "eagle-import:TO92")
      (libsource (lib "eagle-import") (part "-NPN-TO92"))
    )
    (comp (ref "T6")
      (value "2N2222")
      (footprint "eagle-import:TO92")
      (libsource (lib "eagle-import") (part "-NPN-TO92"))
    )
    (comp (ref "T7")
      (value "2N2222")
      (footprint "eagle-import:TO92")
      (libsource (lib "eagle-import") (part "-NPN-TO92"))
    )
    (comp (ref "T8")
      (value "2N2222")
      (footprint "eagle-import:TO92")
      (libsource (lib "eagle-import") (part "-NPN-TO92"))
    )
    (comp (ref "T9")
      (value "2N2222")
      (footprint "eagle-import:TO92")
      (libsource (lib "eagle-import") (part "-NPN-TO92"))
    )
    (comp (ref "T10")
      (value "2N2222")
      (footprint "eagle-import:TO92")
      (libsource (lib "eagle-import") (part "-NPN-TO92"))
    )
    (comp (ref "T11")
      (value "2N2222")
      (footprint "eagle-import:TO92")
      (libsource (lib "eagle-import") (part "-NPN-TO92"))
    )
    (comp (ref "T12")
      (value "2N2222")
      (footprint "eagle-import:TO92")
      (libsource (lib "eagle-import") (part "-NPN-TO92"))
    )
    (comp (ref "T13")
      (value "2N2222")
      (footprint "eagle-import:TO92")
      (libsource (lib "eagle-import") (part "-NPN-TO92"))
    )
    (comp (ref "T14")
      (value "2N2222")
      (footprint "eagle-import:TO92")
      (libsource (lib "eagle-import") (part "-NPN-TO92"))
    )
    (comp (ref "T15")
      (value "2N2222")
      (footprint "eagle-import:TO92")
      (libsource (lib "eagle-import") (part "-NPN-TO92"))
    )
    (comp (ref "T16")
      (value "2N2222")
      (footprint "eagle-import:TO92")
      (libsource (lib "eagle-import") (part "-NPN-TO92"))
    )
    (comp (ref "T17")
      (value "2N2222")
      (footprint "eagle-import:TO92")
      (libsource (lib "eagle-import") (part "-NPN-TO92"))
    )
    (comp (ref "T18")
      (value "2N2222")
      (footprint "eagle-import:TO92")
      (libsource (lib "eagle-import") (part "-NPN-TO92"))
    )
    (comp (ref "T19")
      (value "2N2222")
      (footprint "eagle-import:TO92")
      (libsource (lib "eagle-import") (part "-NPN-TO92"))
    )
    (comp (ref "T20")
      (value "2N2222")
      (footprint "eagle-import:TO92")
      (libsource (lib "eagle-import") (part "-NPN-TO92"))
    )
    (comp (ref "T21")
      (value "2N2222")
      (footprint "eagle-import:TO92")
      (libsource (lib "eagle-import") (part "-NPN-TO92"))
    )
    (comp (ref "T22")
      (value "2N2222")
      (footprint "eagle-import:TO92")
      (libsource (lib "eagle-import") (part "-NPN-TO92"))
    )
    (comp (ref "T23")
      (value "2N2222")
      (footprint "eagle-import:TO92")
      (libsource (lib "eagle-import") (part "-NPN-TO92"))
    )
    (comp (ref "T24")
      (value "2N2222")
      (footprint "eagle-import:TO92")
      (libsource (lib "eagle-import") (part "-NPN-TO92"))
    )
    (comp (ref "T25")
      (value "2N2222")
      (footprint "eagle-import:TO92")
      (libsource (lib "eagle-import") (part "-NPN-TO92"))
    )
    (comp (ref "T26")
      (value "2N2222")
      (footprint "eagle-import:TO92")
      (libsource (lib "eagle-import") (part "-NPN-TO92"))
    )
    (comp (ref "T27")
      (value "2N2222")
      (footprint "eagle-import:TO92")
      (libsource (lib "eagle-import") (part "-NPN-TO92"))
    )
    (comp (ref "T28")
      (value "2N2222")
      (footprint "eagle-import:TO92")
      (libsource (lib "eagle-import") (part "-NPN-TO92"))
    )
    (comp (ref "T29")
      (value "2N2222")
      (footprint "eagle-import:TO92")
      (libsource (lib "eagle-import") (part "-NPN-TO92"))
    )
    (comp (ref "T30")
      (value "2N2222")
      (footprint "eagle-import:TO92")
      (libsource (lib "eagle-import") (part "-NPN-TO92"))
    )
    (comp (ref "T31")
      (value "2N2222")
      (footprint "eagle-import:TO92")
      (libsource (lib "eagle-import") (part "-NPN-TO92"))
    )
    (comp (ref "T32")
      (value "2N2222")
      (footprint "eagle-import:TO92")
      (libsource (lib "eagle-import") (part "-NPN-TO92"))
    )
    (comp (ref "T33")
      (value "2N2222")
      (footprint "eagle-import:TO92")
      (libsource (lib "eagle-import") (part "-NPN-TO92"))
    )
    (comp (ref "T34")
      (value "2N2222")
      (footprint "eagle-import:TO92")
      (libsource (lib "eagle-import") (part "-NPN-TO92"))
    )
    (comp (ref "T35")
      (value "2N2222")
      (footprint "eagle-import:TO92")
      (libsource (lib "eagle-import") (part "-NPN-TO92"))
    )
    (comp (ref "T36")
      (value "2N2222")
      (footprint "eagle-import:TO92")
      (libsource (lib "eagle-import") (part "-NPN-TO92"))
    )
    (comp (ref "T37")
      (value "2N2222")
      (footprint "eagle-import:TO92")
      (libsource (lib "eagle-import") (part "-NPN-TO92"))
    )
    (comp (ref "T38")
      (value "2N2222")
      (footprint "eagle-import:TO92")
      (libsource (lib "eagle-import") (part "-NPN-TO92"))
    )
    (comp (ref "T39")
      (value "2N2222")
      (footprint "eagle-import:TO92")
      (libsource (lib "eagle-import") (part "-NPN-TO92"))
    )
    (comp (ref "T40")
      (value "2N2222")
      (footprint "eagle-import:TO92")
      (libsource (lib "eagle-import") (part "-NPN-TO92"))
    )
    (comp (ref "T41")
      (value "2N2222")
      (footprint "eagle-import:TO92")
      (libsource (lib "eagle-import") (part "-NPN-TO92"))
    )
    (comp (ref "T42")
      (value "2N2222")
      (footprint "eagle-import:TO92")
      (libsource (lib "eagle-import") (part "-NPN-TO92"))
    )
    (comp (ref "T43")
      (value "2N2222")
      (footprint "eagle-import:TO92")
      (libsource (lib "eagle-import") (part "-NPN-TO92"))
    )
    (comp (ref "T44")
      (value "2N2222")
      (footprint "eagle-import:TO92")
      (libsource (lib "eagle-import") (part "-NPN-TO92"))
    )
    (comp (ref "T45")
      (value "2N2222")
      (footprint "eagle-import:TO92")
      (libsource (lib "eagle-import") (part "-NPN-TO92"))
    )
    (comp (ref "T46")
      (value "2N2222")
      (footprint "eagle-import:TO92")
      (libsource (lib "eagle-import") (part "-NPN-TO92"))
    )
    (comp (ref "T47")
      (value "2N2222")
      (footprint "eagle-import:TO92")
      (libsource (lib "eagle-import") (part "-NPN-TO92"))
    )
    (comp (ref "T48")
      (value "2N2222")
      (footprint "eagle-import:TO92")
      (libsource (lib "eagle-import") (part "-NPN-TO92"))
    )
    (comp (ref "T49")
      (value "2N2222")
      (footprint "eagle-import:TO92")
      (libsource (lib "eagle-import") (part "-NPN-TO92"))
    )
    (comp (ref "T50")
      (value "2N2222")
      (footprint "eagle-import:TO92")
      (libsource (lib "eagle-import") (part "-NPN-TO92"))
    )
    (comp (ref "T51")
      (value "2N2222")
      (footprint "eagle-import:TO92")
      (libsource (lib "eagle-import") (part "-NPN-TO92"))
    )
    (comp (ref "T52")
      (value "2N2222")
      (footprint "eagle-import:TO92")
      (libsource (lib "eagle-import") (part "-NPN-TO92"))
    )
    (comp (ref "T53")
      (value "2N2222")
      (footprint "eagle-import:TO92")
      (libsource (lib "eagle-import") (part "-NPN-TO92"))
    )
    (comp (ref "T54")
      (value "2N2222")
      (footprint "eagle-import:TO92")
      (libsource (lib "eagle-import") (part "-NPN-TO92"))
    )
    (comp (ref "T55")
      (value "2N2222")
      (footprint "eagle-import:TO92")
      (libsource (lib "eagle-import") (part "-NPN-TO92"))
    )
    (comp (ref "T56")
      (value "2N2222")
      (footprint "eagle-import:TO92")
      (libsource (lib "eagle-import") (part "-NPN-TO92"))
    )
    (comp (ref "T57")
      (value "2N2222")
      (footprint "eagle-import:TO92")
      (libsource (lib "eagle-import") (part "-NPN-TO92"))
    )
    (comp (ref "T58")
      (value "2N2222")
      (footprint "eagle-import:TO92")
      (libsource (lib "eagle-import") (part "-NPN-TO92"))
    )
    (comp (ref "T59")
      (value "2N2222")
      (footprint "eagle-import:TO92")
      (libsource (lib "eagle-import") (part "-NPN-TO92"))
    )
    (comp (ref "T60")
      (value "2N2222")
      (footprint "eagle-import:TO92")
      (libsource (lib "eagle-import") (part "-NPN-TO92"))
    )
    (comp (ref "T61")
      (value "2N2222")
      (footprint "eagle-import:TO92")
      (libsource (lib "eagle-import") (part "-NPN-TO92"))
    )
    (comp (ref "T62")
      (value "2N2222")
      (footprint "eagle-import:TO92")
      (libsource (lib "eagle-import") (part "-NPN-TO92"))
    )
    (comp (ref "T63")
      (value "2N2222")
      (footprint "eagle-import:TO92")
      (libsource (lib "eagle-import") (part "-NPN-TO92"))
    )
    (comp (ref "T64")
      (value "2N2222")
      (footprint "eagle-import:TO92")
      (libsource (lib "eagle-import") (part "-NPN-TO92"))
    )
    (comp (ref "T65")
      (value "2N2222")
      (footprint "eagle-import:TO92")
      (libsource (lib "eagle-import") (part "-NPN-TO92"))
    )
    (comp (ref "T66")
      (value "2N2222")
      (footprint "eagle-import:TO92")
      (libsource (lib "eagle-import") (part "-NPN-TO92"))
    )
    (comp (ref "T67")
      (value "2N2222")
      (footprint "eagle-import:TO92")
      (libsource (lib "eagle-import") (part "-NPN-TO92"))
    )
    (comp (ref "T68")
      (value "2N2222")
      (footprint "eagle-import:TO92")
      (libsource (lib "eagle-import") (part "-NPN-TO92"))
    )
    (comp (ref "T69")
      (value "2N2222")
      (footprint "eagle-import:TO92")
      (libsource (lib "eagle-import") (part "-NPN-TO92"))
    )
    (comp (ref "T70")
      (value "2N2222")
      (footprint "eagle-import:TO92")
      (libsource (lib "eagle-import") (part "-NPN-TO92"))
    )
    (comp (ref "T71")
      (value "2N2222")
      (footprint "eagle-import:TO92")
      (libsource (lib "eagle-import") (part "-NPN-TO92"))
    )
    (comp (ref "T72")
      (value "2N2222")
      (footprint "eagle-import:TO92")
      (libsource (lib "eagle-import") (part "-NPN-TO92"))
    )
    (comp (ref "T73")
      (value "2N2222")
      (footprint "eagle-import:TO92")
      (libsource (lib "eagle-import") (part "-NPN-TO92"))
    )
    (comp (ref "T74")
      (value "2N2222")
      (footprint "eagle-import:TO92")
      (libsource (lib "eagle-import") (part "-NPN-TO92"))
    )
    (comp (ref "T75")
      (value "2N2222")
      (footprint "eagle-import:TO92")
      (libsource (lib "eagle-import") (part "-NPN-TO92"))
    )
    (comp (ref "T76")
      (value "2N2222")
      (footprint "eagle-import:TO92")
      (libsource (lib "eagle-import") (part "-NPN-TO92"))
    )
    (comp (ref "T77")
      (value "2N2222")
      (footprint "eagle-import:TO92")
      (libsource (lib "eagle-import") (part "-NPN-TO92"))
    )
    (comp (ref "T78")
      (value "2N2222")
      (footprint "eagle-import:TO92")
      (libsource (lib "eagle-import") (part "-NPN-TO92"))
    )
    (comp (ref "T79")
      (value "2N2222")
      (footprint "eagle-import:TO92")
      (libsource (lib "eagle-import") (part "-NPN-TO92"))
    )
    (comp (ref "T80")
      (value "2N2222")
      (footprint "eagle-import:TO92")
      (libsource (lib "eagle-import") (part "-NPN-TO92"))
    )
    (comp (ref "T81")
      (value "2N2222")
      (footprint "eagle-import:TO92")
      (libsource (lib "eagle-import") (part "-NPN-TO92"))
    )
    (comp (ref "T82")
      (value "2N2222")
      (footprint "eagle-import:TO92")
      (libsource (lib "eagle-import") (part "-NPN-TO92"))
    )
    (comp (ref "T83")
      (value "2N2222")
      (footprint "eagle-import:TO92")
      (libsource (lib "eagle-import") (part "-NPN-TO92"))
    )
    (comp (ref "T84")
      (value "2N2222")
      (footprint "eagle-import:TO92")
      (libsource (lib "eagle-import") (part "-NPN-TO92"))
    )
    (comp (ref "T85")
      (value "2N2222")
      (footprint "eagle-import:TO92")
      (libsource (lib "eagle-import") (part "-NPN-TO92"))
    )
    (comp (ref "T86")
      (value "2N2222")
      (footprint "eagle-import:TO92")
      (libsource (lib "eagle-import") (part "-NPN-TO92"))
    )
    (comp (ref "T87")
      (value "2N2222")
      (footprint "eagle-import:TO92")
      (libsource (lib "eagle-import") (part "-NPN-TO92"))
    )
    (comp (ref "T88")
      (value "2N2222")
      (footprint "eagle-import:TO92")
      (libsource (lib "eagle-import") (part "-NPN-TO92"))
    )
    (comp (ref "T89")
      (value "2N2222")
      (footprint "eagle-import:TO92")
      (libsource (lib "eagle-import") (part "-NPN-TO92"))
    )
    (comp (ref "TAD")
      (value "BULB")
      (footprint "eagle-import:BULB")
      (libsource (lib "eagle-import") (part "BULB"))
    )
    (comp (ref "WORDCOUNT")
      (value "BULB")
      (footprint "eagle-import:BULB")
      (libsource (lib "eagle-import") (part "BULB"))
    )
    (comp (ref "C40")
      (value "MA17-2")
      (footprint "eagle-import:MA17-2")
      (libsource (lib "eagle-import") (part "MA17-2"))
    )
    (comp (ref "D40")
      (value "MA17-2")
      (footprint "eagle-import:MA17-2")
      (libsource (lib "eagle-import") (part "MA17-2"))
    )
    (comp (ref "E40")
      (value "MA17-2")
      (footprint "eagle-import:MA17-2")
      (libsource (lib "eagle-import") (part "MA17-2"))
    )
    (comp (ref "F40")
      (value "MA17-2")
      (footprint "eagle-import:MA17-2")
      (libsource (lib "eagle-import") (part "MA17-2"))
    )
  )
  (nets
    (net (code "1") (name "+15V") (class "Default")
      (node (ref "+V1") (pin "1") (pinfunction "1_1") (pintype "passive"))
      (node (ref "+V2") (pin "1") (pinfunction "1_1") (pintype "passive"))
      (node (ref "+V3") (pin "1") (pinfunction "1_1") (pintype "passive"))
      (node (ref "+V4") (pin "1") (pinfunction "1_1") (pintype "passive"))
      (node (ref "R1") (pin "1") (pinfunction "1_1") (pintype "passive"))
      (node (ref "R10") (pin "1") (pinfunction "1_1") (pintype "passive"))
      (node (ref "R11") (pin "1") (pinfunction "1_1") (pintype "passive"))
      (node (ref "R12") (pin "1") (pinfunction "1_1") (pintype "passive"))
      (node (ref "R13") (pin "1") (pinfunction "1_1") (pintype "passive"))
      (node (ref "R14") (pin "1") (pinfunction "1_1") (pintype "passive"))
      (node (ref "R15") (pin "1") (pinfunction "1_1") (pintype "passive"))
      (node (ref "R16") (pin "1") (pinfunction "1_1") (pintype "passive"))
      (node (ref "R17") (pin "1") (pinfunction "1_1") (pintype "passive"))
      (node (ref "R18") (pin "1") (pinfunction "1_1") (pintype "passive"))
      (node (ref "R19") (pin "1") (pinfunction "1_1") (pintype "passive"))
      (node (ref "R2") (pin "1") (pinfunction "1_1") (pintype "passive"))
      (node (ref "R20") (pin "1") (pinfunction "1_1") (pintype "passive"))
      (node (ref "R21") (pin "1") (pinfunction "1_1") (pintype "passive"))
      (node (ref "R22") (pin "1") (pinfunction "1_1") (pintype "passive"))
      (node (ref "R23") (pin "1") (pinfunction "1_1") (pintype "passive"))
      (node (ref "R24") (pin "1") (pinfunction "1_1") (pintype "passive"))
      (node (ref "R25") (pin "1") (pinfunction "1_1") (pintype "passive"))
      (node (ref "R26") (pin "1") (pinfunction "1_1") (pintype "passive"))
      (node (ref "R27") (pin "1") (pinfunction "1_1") (pintype "passive"))
      (node (ref "R28") (pin "1") (pinfunction "1_1") (pintype "passive"))
      (node (ref "R29") (pin "1") (pinfunction "1_1") (pintype "passive"))
      (node (ref "R3") (pin "1") (pinfunction "1_1") (pintype "passive"))
      (node (ref "R30") (pin "1") (pinfunction "1_1") (pintype "passive"))
      (node (ref "R31") (pin "1") (pinfunction "1_1") (pintype "passive"))
      (node (ref "R32") (pin "1") (pinfunction "1_1") (pintype "passive"))
      (node (ref "R33") (pin "1") (pinfunction "1_1") (pintype "passive"))
      (node (ref "R34") (pin "1") (pinfunction "1_1") (pintype "passive"))
      (node (ref "R35") (pin "1") (pinfunction "1_1") (pintype "passive"))
      (node (ref "R36") (pin "1") (pinfunction "1_1") (pintype "passive"))
      (node (ref "R37") (pin "1") (pinfunction "1_1") (pintype "passive"))
      (node (ref "R38") (pin "1") (pinfunction "1_1") (pintype "passive"))
      (node (ref "R39") (pin "1") (pinfunction "1_1") (pintype "passive"))
      (node (ref "R4") (pin "1") (pinfunction "1_1") (pintype "passive"))
      (node (ref "R40") (pin "1") (pinfunction "1_1") (pintype "passive"))
      (node (ref "R41") (pin "1") (pinfunction "1_1") (pintype "passive"))
      (node (ref "R42") (pin "1") (pinfunction "1_1") (pintype "passive"))
      (node (ref "R43") (pin "1") (pinfunction "1_1") (pintype "passive"))
      (node (ref "R44") (pin "1") (pinfunction "1_1") (pintype "passive"))
      (node (ref "R45") (pin "1") (pinfunction "1_1") (pintype "passive"))
      (node (ref "R46") (pin "1") (pinfunction "1_1") (pintype "passive"))
      (node (ref "R47") (pin "1") (pinfunction "1_1") (pintype "passive"))
      (node (ref "R48") (pin "1") (pinfunction "1_1") (pintype "passive"))
      (node (ref "R49") (pin "1") (pinfunction "1_1") (pintype "passive"))
      (node (ref "R5") (pin "1") (pinfunction "1_1") (pintype "passive"))
      (node (ref "R50") (pin "1") (pinfunction "1_1") (pintype "passive"))
      (node (ref "R51") (pin "1") (pinfunction "1_1") (pintype "passive"))
      (node (ref "R52") (pin "1") (pinfunction "1_1") (pintype "passive"))
      (node (ref "R53") (pin "1") (pinfunction "1_1") (pintype "passive"))
      (node (ref "R54") (pin "1") (pinfunction "1_1") (pintype "passive"))
      (node (ref "R55") (pin "1") (pinfunction "1_1") (pintype "passive"))
      (node (ref "R56") (pin "1") (pinfunction "1_1") (pintype "passive"))
      (node (ref "R57") (pin "1") (pinfunction "1_1") (pintype "passive"))
      (node (ref "R58") (pin "1") (pinfunction "1_1") (pintype "passive"))
      (node (ref "R59") (pin "1") (pinfunction "1_1") (pintype "passive"))
      (node (ref "R6") (pin "1") (pinfunction "1_1") (pintype "passive"))
      (node (ref "R60") (pin "1") (pinfunction "1_1") (pintype "passive"))
      (node (ref "R61") (pin "1") (pinfunction "1_1") (pintype "passive"))
      (node (ref "R62") (pin "1") (pinfunction "1_1") (pintype "passive"))
      (node (ref "R63") (pin "1") (pinfunction "1_1") (pintype "passive"))
      (node (ref "R64") (pin "1") (pinfunction "1_1") (pintype "passive"))
      (node (ref "R65") (pin "1") (pinfunction "1_1") (pintype "passive"))
      (node (ref "R66") (pin "1") (pinfunction "1_1") (pintype "passive"))
      (node (ref "R67") (pin "1") (pinfunction "1_1") (pintype "passive"))
      (node (ref "R68") (pin "1") (pinfunction "1_1") (pintype "passive"))
      (node (ref "R69") (pin "1") (pinfunction "1_1") (pintype "passive"))
      (node (ref "R7") (pin "1") (pinfunction "1_1") (pintype "passive"))
      (node (ref "R70") (pin "1") (pinfunction "1_1") (pintype "passive"))
      (node (ref "R71") (pin "1") (pinfunction "1_1") (pintype "passive"))
      (node (ref "R72") (pin "1") (pinfunction "1_1") (pintype "passive"))
      (node (ref "R73") (pin "1") (pinfunction "1_1") (pintype "passive"))
      (node (ref "R74") (pin "1") (pinfunction "1_1") (pintype "passive"))
      (node (ref "R75") (pin "1") (pinfunction "1_1") (pintype "passive"))
      (node (ref "R76") (pin "1") (pinfunction "1_1") (pintype "passive"))
      (node (ref "R77") (pin "1") (pinfunction "1_1") (pintype "passive"))
      (node (ref "R78") (pin "1") (pinfunction "1_1") (pintype "passive"))
      (node (ref "R79") (pin "1") (pinfunction "1_1") (pintype "passive"))
      (node (ref "R8") (pin "1") (pinfunction "1_1") (pintype "passive"))
      (node (ref "R80") (pin "1") (pinfunction "1_1") (pintype "passive"))
      (node (ref "R81") (pin "1") (pinfunction "1_1") (pintype "passive"))
      (node (ref "R82") (pin "1") (pinfunction "1_1") (pintype "passive"))
      (node (ref "R83") (pin "1") (pinfunction "1_1") (pintype "passive"))
      (node (ref "R84") (pin "1") (pinfunction "1_1") (pintype "passive"))
      (node (ref "R85") (pin "1") (pinfunction "1_1") (pintype "passive"))
      (node (ref "R86") (pin "1") (pinfunction "1_1") (pintype "passive"))
      (node (ref "R87") (pin "1") (pinfunction "1_1") (pintype "passive"))
      (node (ref "R88") (pin "1") (pinfunction "1_1") (pintype "passive"))
      (node (ref "R89") (pin "1") (pinfunction "1_1") (pintype "passive"))
      (node (ref "R9") (pin "1") (pinfunction "1_1") (pintype "passive"))
    )
    (net (code "2") (name "AC0") (class "Default")
      (node (ref "D40TOP") (pin "4") (pinfunction "1_4") (pintype "passive"))
      (node (ref "E40") (pin "7") (pinfunction "7_7") (pintype "passive"))
      (node (ref "T43") (pin "2") (pinfunction "B_2") (pintype "passive"))
    )
    (net (code "3") (name "AC1") (class "Default")
      (node (ref "D40BOT") (pin "2") (pinfunction "1_2") (pintype "passive"))
      (node (ref "E40") (pin "4") (pinfunction "4_4") (pintype "passive"))
      (node (ref "T44") (pin "2") (pinfunction "B_2") (pintype "passive"))
    )
    (net (code "4") (name "AC2") (class "Default")
      (node (ref "D40TOP") (pin "12") (pinfunction "1_12") (pintype "passive"))
      (node (ref "E40") (pin "21") (pinfunction "21_21") (pintype "passive"))
      (node (ref "T45") (pin "2") (pinfunction "B_2") (pintype "passive"))
    )
    (net (code "5") (name "AC3") (class "Default")
      (node (ref "D40BOT") (pin "9") (pinfunction "1_9") (pintype "passive"))
      (node (ref "E40") (pin "14") (pinfunction "14_14") (pintype "passive"))
      (node (ref "T46") (pin "2") (pinfunction "B_2") (pintype "passive"))
    )
    (net (code "6") (name "AC4") (class "Default")
      (node (ref "D40TOP") (pin "17") (pinfunction "1_17") (pintype "passive"))
      (node (ref "E40") (pin "31") (pinfunction "31_31") (pintype "passive"))
      (node (ref "T47") (pin "2") (pinfunction "B_2") (pintype "passive"))
    )
    (net (code "7") (name "AC5") (class "Default")
      (node (ref "D40BOT") (pin "16") (pinfunction "1_16") (pintype "passive"))
      (node (ref "E40") (pin "28") (pinfunction "28_28") (pintype "passive"))
      (node (ref "T48") (pin "2") (pinfunction "B_2") (pintype "passive"))
    )
    (net (code "8") (name "AC6") (class "Default")
      (node (ref "E40TOP") (pin "4") (pinfunction "1_4") (pintype "passive"))
      (node (ref "F40") (pin "7") (pinfunction "7_7") (pintype "passive"))
      (node (ref "T49") (pin "2") (pinfunction "B_2") (pintype "passive"))
    )
    (net (code "9") (name "AC7") (class "Default")
      (node (ref "E40BOT") (pin "2") (pinfunction "1_2") (pintype "passive"))
      (node (ref "F40") (pin "4") (pinfunction "4_4") (pintype "passive"))
      (node (ref "T50") (pin "2") (pinfunction "B_2") (pintype "passive"))
    )
    (net (code "10") (name "AC8") (class "Default")
      (node (ref "E40TOP") (pin "12") (pinfunction "1_12") (pintype "passive"))
      (node (ref "F40") (pin "21") (pinfunction "21_21") (pintype "passive"))
      (node (ref "T51") (pin "2") (pinfunction "B_2") (pintype "passive"))
    )
    (net (code "11") (name "AC9") (class "Default")
      (node (ref "E40BOT") (pin "9") (pinfunction "1_9") (pintype "passive"))
      (node (ref "F40") (pin "14") (pinfunction "14_14") (pintype "passive"))
      (node (ref "T52") (pin "2") (pinfunction "B_2") (pintype "passive"))
    )
    (net (code "12") (name "AC10") (class "Default")
      (node (ref "E40TOP") (pin "17") (pinfunction "1_17") (pintype "passive"))
      (node (ref "F40") (pin "31") (pinfunction "31_31") (pintype "passive"))
      (node (ref "T53") (pin "2") (pinfunction "B_2") (pintype "passive"))
    )
    (net (code "13") (name "AC11") (class "Default")
      (node (ref "E40BOT") (pin "16") (pinfunction "1_16") (pintype "passive"))
      (node (ref "F40") (pin "28") (pinfunction "28_28") (pintype "passive"))
      (node (ref "T54") (pin "2") (pinfunction "B_2") (pintype "passive"))
    )
    (net (code "14") (name "AND") (class "Default")
      (node (ref "D40") (pin "2") (pinfunction "2_2") (pintype "passive"))
      (node (ref "F40BOT") (pin "1") (pinfunction "1_1") (pintype "passive"))
      (node (ref "T82") (pin "2") (pinfunction "B_2") (pintype "passive"))
    )
    (net (code "15") (name "BREAK") (class "Default")
      (node (ref "D40") (pin "22") (pinfunction "22_22") (pintype "passive"))
      (node (ref "F40BOT") (pin "12") (pinfunction "1_12") (pintype "passive"))
      (node (ref "T81") (pin "2") (pinfunction "B_2") (pintype "passive"))
    )
    (net (code "16") (name "CA") (class "Default")
      (node (ref "D40") (pin "32") (pinfunction "32_32") (pintype "passive"))
      (node (ref "F40BOT") (pin "18") (pinfunction "1_18") (pintype "passive"))
      (node (ref "T80") (pin "2") (pinfunction "B_2") (pintype "passive"))
    )
    (net (code "17") (name "DCA") (class "Default")
      (node (ref "D40") (pin "8") (pinfunction "8_8") (pintype "passive"))
      (node (ref "F40BOT") (pin "4") (pinfunction "1_4") (pintype "passive"))
      (node (ref "T85") (pin "2") (pinfunction "B_2") (pintype "passive"))
    )
    (net (code "18") (name "DEFER") (class "Default")
      (node (ref "D40") (pin "26") (pinfunction "26_26") (pintype "passive"))
      (node (ref "F40BOT") (pin "15") (pinfunction "1_15") (pintype "passive"))
      (node (ref "T78") (pin "2") (pinfunction "B_2") (pintype "passive"))
    )
    (net (code "19") (name "DF0") (class "Default")
      (node (ref "C40") (pin "1") (pinfunction "1_1") (pintype "passive"))
      (node (ref "C40TOP") (pin "1") (pinfunction "1_1") (pintype "passive"))
      (node (ref "T1") (pin "2") (pinfunction "B_2") (pintype "passive"))
    )
    (net (code "20") (name "DF1") (class "Default")
      (node (ref "C40") (pin "10") (pinfunction "10_10") (pintype "passive"))
      (node (ref "C40BOT") (pin "5") (pinfunction "1_5") (pintype "passive"))
      (node (ref "T2") (pin "2") (pinfunction "B_2") (pintype "passive"))
    )
    (net (code "21") (name "DF2") (class "Default")
      (node (ref "C40") (pin "11") (pinfunction "11_11") (pintype "passive"))
      (node (ref "C40TOP") (pin "6") (pinfunction "1_6") (pintype "passive"))
      (node (ref "T3") (pin "2") (pinfunction "B_2") (pintype "passive"))
    )
    (net (code "22") (name "EXECUTE") (class "Default")
      (node (ref "D40") (pin "28") (pinfunction "28_28") (pintype "passive"))
      (node (ref "F40BOT") (pin "16") (pinfunction "1_16") (pintype "passive"))
      (node (ref "T77") (pin "2") (pinfunction "B_2") (pintype "passive"))
    )
    (net (code "23") (name "FETCH") (class "Default")
      (node (ref "D40") (pin "24") (pinfunction "24_24") (pintype "passive"))
      (node (ref "F40BOT") (pin "14") (pinfunction "1_14") (pintype "passive"))
      (node (ref "T76") (pin "2") (pinfunction "B_2") (pintype "passive"))
    )
    (net (code "24") (name "GND") (class "Default")
      (node (ref "C40") (pin "17") (pinfunction "17_17") (pintype "passive"))
      (node (ref "C40") (pin "18") (pinfunction "18_18") (pintype "passive"))
      (node (ref "C40") (pin "19") (pinfunction "19_19") (pintype "passive"))
      (node (ref "C40") (pin "20") (pinfunction "20_20") (pintype "passive"))
      (node (ref "C40BOT") (pin "13") (pinfunction "1_13") (pintype "passive"))
      (node (ref "D40") (pin "17") (pinfunction "17_17") (pintype "passive"))
      (node (ref "D40") (pin "18") (pinfunction "18_18") (pintype "passive"))
      (node (ref "D40") (pin "19") (pinfunction "19_19") (pintype "passive"))
      (node (ref "D40") (pin "20") (pinfunction "20_20") (pintype "passive"))
      (node (ref "D40BOT") (pin "13") (pinfunction "1_13") (pintype "passive"))
      (node (ref "E40") (pin "17") (pinfunction "17_17") (pintype "passive"))
      (node (ref "E40") (pin "18") (pinfunction "18_18") (pintype "passive"))
      (node (ref "E40") (pin "19") (pinfunction "19_19") (pintype "passive"))
      (node (ref "E40") (pin "20") (pinfunction "20_20") (pintype "passive"))
      (node (ref "E40BOT") (pin "13") (pinfunction "1_13") (pintype "passive"))
      (node (ref "F40") (pin "17") (pinfunction "17_17") (pintype "passive"))
      (node (ref "F40") (pin "18") (pinfunction "18_18") (pintype "passive"))
      (node (ref "F40") (pin "19") (pinfunction "19_19") (pintype "passive"))
      (node (ref "F40") (pin "20") (pinfunction "20_20") (pintype "passive"))
      (node (ref "F40BOT") (pin "13") (pinfunction "1_13") (pintype "passive"))
      (node (ref "GND1") (pin "1") (pinfunction "1_1") (pintype "passive"))
      (node (ref "GND2") (pin "1") (pinfunction "1_1") (pintype "passive"))
      (node (ref "GND3") (pin "1") (pinfunction "1_1") (pintype "passive"))
      (node (ref "GND4") (pin "1") (pinfunction "1_1") (pintype "passive"))
      (node (ref "T1") (pin "1") (pinfunction "E_1") (pintype "passive"))
      (node (ref "T10") (pin "1") (pinfunction "E_1") (pintype "passive"))
      (node (ref "T11") (pin "1") (pinfunction "E_1") (pintype "passive"))
      (node (ref "T12") (pin "1") (pinfunction "E_1") (pintype "passive"))
      (node (ref "T13") (pin "1") (pinfunction "E_1") (pintype "passive"))
      (node (ref "T14") (pin "1") (pinfunction "E_1") (pintype "passive"))
      (node (ref "T15") (pin "1") (pinfunction "E_1") (pintype "passive"))
      (node (ref "T16") (pin "1") (pinfunction "E_1") (pintype "passive"))
      (node (ref "T17") (pin "1") (pinfunction "E_1") (pintype "passive"))
      (node (ref "T18") (pin "1") (pinfunction "E_1") (pintype "passive"))
      (node (ref "T19") (pin "1") (pinfunction "E_1") (pintype "passive"))
      (node (ref "T2") (pin "1") (pinfunction "E_1") (pintype "passive"))
      (node (ref "T20") (pin "1") (pinfunction "E_1") (pintype "passive"))
      (node (ref "T21") (pin "1") (pinfunction "E_1") (pintype "passive"))
      (node (ref "T22") (pin "1") (pinfunction "E_1") (pintype "passive"))
      (node (ref "T23") (pin "1") (pinfunction "E_1") (pintype "passive"))
      (node (ref "T24") (pin "1") (pinfunction "E_1") (pintype "passive"))
      (node (ref "T25") (pin "1") (pinfunction "E_1") (pintype "passive"))
      (node (ref "T26") (pin "1") (pinfunction "E_1") (pintype "passive"))
      (node (ref "T27") (pin "1") (pinfunction "E_1") (pintype "passive"))
      (node (ref "T28") (pin "1") (pinfunction "E_1") (pintype "passive"))
      (node (ref "T29") (pin "1") (pinfunction "E_1") (pintype "passive"))
      (node (ref "T3") (pin "1") (pinfunction "E_1") (pintype "passive"))
      (node (ref "T30") (pin "1") (pinfunction "E_1") (pintype "passive"))
      (node (ref "T31") (pin "1") (pinfunction "E_1") (pintype "passive"))
      (node (ref "T32") (pin "1") (pinfunction "E_1") (pintype "passive"))
      (node (ref "T33") (pin "1") (pinfunction "E_1") (pintype "passive"))
      (node (ref "T34") (pin "1") (pinfunction "E_1") (pintype "passive"))
      (node (ref "T35") (pin "1") (pinfunction "E_1") (pintype "passive"))
      (node (ref "T36") (pin "1") (pinfunction "E_1") (pintype "passive"))
      (node (ref "T37") (pin "1") (pinfunction "E_1") (pintype "passive"))
      (node (ref "T38") (pin "1") (pinfunction "E_1") (pintype "passive"))
      (node (ref "T39") (pin "1") (pinfunction "E_1") (pintype "passive"))
      (node (ref "T4") (pin "1") (pinfunction "E_1") (pintype "passive"))
      (node (ref "T40") (pin "1") (pinfunction "E_1") (pintype "passive"))
      (node (ref "T41") (pin "1") (pinfunction "E_1") (pintype "passive"))
      (node (ref "T42") (pin "1") (pinfunction "E_1") (pintype "passive"))
      (node (ref "T43") (pin "1") (pinfunction "E_1") (pintype "passive"))
      (node (ref "T44") (pin "1") (pinfunction "E_1") (pintype "passive"))
      (node (ref "T45") (pin "1") (pinfunction "E_1") (pintype "passive"))
      (node (ref "T46") (pin "1") (pinfunction "E_1") (pintype "passive"))
      (node (ref "T47") (pin "1") (pinfunction "E_1") (pintype "passive"))
      (node (ref "T48") (pin "1") (pinfunction "E_1") (pintype "passive"))
      (node (ref "T49") (pin "1") (pinfunction "E_1") (pintype "passive"))
      (node (ref "T5") (pin "1") (pinfunction "E_1") (pintype "passive"))
      (node (ref "T50") (pin "1") (pinfunction "E_1") (pintype "passive"))
      (node (ref "T51") (pin "1") (pinfunction "E_1") (pintype "passive"))
      (node (ref "T52") (pin "1") (pinfunction "E_1") (pintype "passive"))
      (node (ref "T53") (pin "1") (pinfunction "E_1") (pintype "passive"))
      (node (ref "T54") (pin "1") (pinfunction "E_1") (pintype "passive"))
      (node (ref "T55") (pin "1") (pinfunction "E_1") (pintype "passive"))
      (node (ref "T56") (pin "1") (pinfunction "E_1") (pintype "passive"))
      (node (ref "T57") (pin "1") (pinfunction "E_1") (pintype "passive"))
      (node (ref "T58") (pin "1") (pinfunction "E_1") (pintype "passive"))
      (node (ref "T59") (pin "1") (pinfunction "E_1") (pintype "passive"))
      (node (ref "T6") (pin "1") (pinfunction "E_1") (pintype "passive"))
      (node (ref "T60") (pin "1") (pinfunction "E_1") (pintype "passive"))
      (node (ref "T61") (pin "1") (pinfunction "E_1") (pintype "passive"))
      (node (ref "T62") (pin "1") (pinfunction "E_1") (pintype "passive"))
      (node (ref "T63") (pin "1") (pinfunction "E_1") (pintype "passive"))
      (node (ref "T64") (pin "1") (pinfunction "E_1") (pintype "passive"))
      (node (ref "T65") (pin "1") (pinfunction "E_1") (pintype "passive"))
      (node (ref "T66") (pin "1") (pinfunction "E_1") (pintype "passive"))
      (node (ref "T67") (pin "1") (pinfunction "E_1") (pintype "passive"))
      (node (ref "T68") (pin "1") (pinfunction "E_1") (pintype "passive"))
      (node (ref "T69") (pin "1") (pinfunction "E_1") (pintype "passive"))
      (node (ref "T7") (pin "1") (pinfunction "E_1") (pintype "passive"))
      (node (ref "T70") (pin "1") (pinfunction "E_1") (pintype "passive"))
      (node (ref "T71") (pin "1") (pinfunction "E_1") (pintype "passive"))
      (node (ref "T72") (pin "1") (pinfunction "E_1") (pintype "passive"))
      (node (ref "T73") (pin "1") (pinfunction "E_1") (pintype "passive"))
      (node (ref "T74") (pin "1") (pinfunction "E_1") (pintype "passive"))
      (node (ref "T75") (pin "1") (pinfunction "E_1") (pintype "passive"))
      (node (ref "T76") (pin "1") (pinfunction "E_1") (pintype "passive"))
      (node (ref "T77") (pin "1") (pinfunction "E_1") (pintype "passive"))
      (node (ref "T78") (pin "1") (pinfunction "E_1") (pintype "passive"))
      (node (ref "T79") (pin "1") (pinfunction "E_1") (pintype "passive"))
      (node (ref "T8") (pin "1") (pinfunction "E_1") (pintype "passive"))
      (node (ref "T80") (pin "1") (pinfunction "E_1") (pintype "passive"))
      (node (ref "T81") (pin "1") (pinfunction "E_1") (pintype "passive"))
      (node (ref "T82") (pin "1") (pinfunction "E_1") (pintype "passive"))
      (node (ref "T83") (pin "1") (pinfunction "E_1") (pintype "passive"))
      (node (ref "T84") (pin "1") (pinfunction "E_1") (pintype "passive"))
      (node (ref "T85") (pin "1") (pinfunction "E_1") (pintype "passive"))
      (node (ref "T86") (pin "1") (pinfunction "E_1") (pintype "passive"))
      (node (ref "T87") (pin "1") (pinfunction "E_1") (pintype "passive"))
      (node (ref "T88") (pin "1") (pinfunction "E_1") (pintype "passive"))
      (node (ref "T89") (pin "1") (pinfunction "E_1") (pintype "passive"))
      (node (ref "T9") (pin "1") (pinfunction "E_1") (pintype "passive"))
    )
    (net (code "25") (name "IF0") (class "Default")
      (node (ref "C40") (pin "24") (pinfunction "24_24") (pintype "passive"))
      (node (ref "C40BOT") (pin "14") (pinfunction "1_14") (pintype "passive"))
      (node (ref "T4") (pin "2") (pinfunction "B_2") (pintype "passive"))
    )
    (net (code "26") (name "IF1") (class "Default")
      (node (ref "C40") (pin "25") (pinfunction "25_25") (pintype "passive"))
      (node (ref "C40TOP") (pin "14") (pinfunction "1_14") (pintype "passive"))
      (node (ref "T5") (pin "2") (pinfunction "B_2") (pintype "passive"))
    )
    (net (code "27") (name "IF2") (class "Default")
      (node (ref "C40") (pin "34") (pinfunction "34_34") (pintype "passive"))
      (node (ref "C40BOT") (pin "19") (pinfunction "1_19") (pintype "passive"))
      (node (ref "T6") (pin "2") (pinfunction "B_2") (pintype "passive"))
    )
    (net (code "28") (name "ION") (class "Default")
      (node (ref "D40") (pin "34") (pinfunction "34_34") (pintype "passive"))
      (node (ref "F40BOT") (pin "19") (pinfunction "1_19") (pintype "passive"))
      (node (ref "T73") (pin "2") (pinfunction "B_2") (pintype "passive"))
    )
    (net (code "29") (name "IOT") (class "Default")
      (node (ref "D40") (pin "23") (pinfunction "23_23") (pintype "passive"))
      (node (ref "F40TOP") (pin "13") (pinfunction "1_13") (pintype "passive"))
      (node (ref "T88") (pin "2") (pinfunction "B_2") (pintype "passive"))
    )
    (net (code "30") (name "ISZ") (class "Default")
      (node (ref "D40") (pin "6") (pinfunction "6_6") (pintype "passive"))
      (node (ref "F40BOT") (pin "3") (pinfunction "1_3") (pintype "passive"))
      (node (ref "T84") (pin "2") (pinfunction "B_2") (pintype "passive"))
    )
    (net (code "31") (name "JMP") (class "Default")
      (node (ref "D40") (pin "12") (pinfunction "12_12") (pintype "passive"))
      (node (ref "F40BOT") (pin "6") (pinfunction "1_6") (pintype "passive"))
      (node (ref "T87") (pin "2") (pinfunction "B_2") (pintype "passive"))
    )
    (net (code "32") (name "JMS") (class "Default")
      (node (ref "D40") (pin "10") (pinfunction "10_10") (pintype "passive"))
      (node (ref "F40BOT") (pin "5") (pinfunction "1_5") (pintype "passive"))
      (node (ref "T86") (pin "2") (pinfunction "B_2") (pintype "passive"))
    )
    (net (code "33") (name "LINK") (class "Default")
      (node (ref "C40") (pin "28") (pinfunction "28_28") (pintype "passive"))
      (node (ref "C40BOT") (pin "16") (pinfunction "1_16") (pintype "passive"))
      (node (ref "T72") (pin "2") (pinfunction "B_2") (pintype "passive"))
    )
    (net (code "34") (name "MA0") (class "Default")
      (node (ref "D40TOP") (pin "2") (pinfunction "1_2") (pintype "passive"))
      (node (ref "E40") (pin "3") (pinfunction "3_3") (pintype "passive"))
      (node (ref "T19") (pin "2") (pinfunction "B_2") (pintype "passive"))
    )
    (net (code "35") (name "MA1") (class "Default")
      (node (ref "D40BOT") (pin "4") (pinfunction "1_4") (pintype "passive"))
      (node (ref "E40") (pin "8") (pinfunction "8_8") (pintype "passive"))
      (node (ref "T20") (pin "2") (pinfunction "B_2") (pintype "passive"))
    )
    (net (code "36") (name "MA2") (class "Default")
      (node (ref "D40TOP") (pin "7") (pinfunction "1_7") (pintype "passive"))
      (node (ref "E40") (pin "13") (pinfunction "13_13") (pintype "passive"))
      (node (ref "T21") (pin "2") (pinfunction "B_2") (pintype "passive"))
    )
    (net (code "37") (name "MA3") (class "Default")
      (node (ref "D40BOT") (pin "12") (pinfunction "1_12") (pintype "passive"))
      (node (ref "E40") (pin "22") (pinfunction "22_22") (pintype "passive"))
      (node (ref "T22") (pin "2") (pinfunction "B_2") (pintype "passive"))
    )
    (net (code "38") (name "MA4") (class "Default")
      (node (ref "D40TOP") (pin "15") (pinfunction "1_15") (pintype "passive"))
      (node (ref "E40") (pin "27") (pinfunction "27_27") (pintype "passive"))
      (node (ref "T23") (pin "2") (pinfunction "B_2") (pintype "passive"))
    )
    (net (code "39") (name "MA5") (class "Default")
      (node (ref "D40BOT") (pin "18") (pinfunction "1_18") (pintype "passive"))
      (node (ref "E40") (pin "32") (pinfunction "32_32") (pintype "passive"))
      (node (ref "T24") (pin "2") (pinfunction "B_2") (pintype "passive"))
    )
    (net (code "40") (name "MA6") (class "Default")
      (node (ref "E40TOP") (pin "2") (pinfunction "1_2") (pintype "passive"))
      (node (ref "F40") (pin "3") (pinfunction "3_3") (pintype "passive"))
      (node (ref "T25") (pin "2") (pinfunction "B_2") (pintype "passive"))
    )
    (net (code "41") (name "MA7") (class "Default")
      (node (ref "E40BOT") (pin "4") (pinfunction "1_4") (pintype "passive"))
      (node (ref "F40") (pin "8") (pinfunction "8_8") (pintype "passive"))
      (node (ref "T26") (pin "2") (pinfunction "B_2") (pintype "passive"))
    )
    (net (code "42") (name "MA8") (class "Default")
      (node (ref "E40TOP") (pin "7") (pinfunction "1_7") (pintype "passive"))
      (node (ref "F40") (pin "13") (pinfunction "13_13") (pintype "passive"))
      (node (ref "T27") (pin "2") (pinfunction "B_2") (pintype "passive"))
    )
    (net (code "43") (name "MA9") (class "Default")
      (node (ref "E40BOT") (pin "12") (pinfunction "1_12") (pintype "passive"))
      (node (ref "F40") (pin "22") (pinfunction "22_22") (pintype "passive"))
      (node (ref "T28") (pin "2") (pinfunction "B_2") (pintype "passive"))
    )
    (net (code "44") (name "MA10") (class "Default")
      (node (ref "E40TOP") (pin "15") (pinfunction "1_15") (pintype "passive"))
      (node (ref "F40") (pin "27") (pinfunction "27_27") (pintype "passive"))
      (node (ref "T29") (pin "2") (pinfunction "B_2") (pintype "passive"))
    )
    (net (code "45") (name "MA11") (class "Default")
      (node (ref "E40BOT") (pin "18") (pinfunction "1_18") (pintype "passive"))
      (node (ref "F40") (pin "32") (pinfunction "32_32") (pintype "passive"))
      (node (ref "T30") (pin "2") (pinfunction "B_2") (pintype "passive"))
    )
    (net (code "46") (name "MB0") (class "Default")
      (node (ref "D40TOP") (pin "3") (pinfunction "1_3") (pintype "passive"))
      (node (ref "E40") (pin "5") (pinfunction "5_5") (pintype "passive"))
      (node (ref "T31") (pin "2") (pinfunction "B_2") (pintype "passive"))
    )
    (net (code "47") (name "MB1") (class "Default")
      (node (ref "D40BOT") (pin "3") (pinfunction "1_3") (pintype "passive"))
      (node (ref "E40") (pin "6") (pinfunction "6_6") (pintype "passive"))
      (node (ref "T32") (pin "2") (pinfunction "B_2") (pintype "passive"))
    )
    (net (code "48") (name "MB2") (class "Default")
      (node (ref "D40TOP") (pin "8") (pinfunction "1_8") (pintype "passive"))
      (node (ref "E40") (pin "15") (pinfunction "15_15") (pintype "passive"))
      (node (ref "T33") (pin "2") (pinfunction "B_2") (pintype "passive"))
    )
    (net (code "49") (name "MB3") (class "Default")
      (node (ref "D40BOT") (pin "11") (pinfunction "1_11") (pintype "passive"))
      (node (ref "E40") (pin "16") (pinfunction "16_16") (pintype "passive"))
      (node (ref "T34") (pin "2") (pinfunction "B_2") (pintype "passive"))
    )
    (net (code "50") (name "MB4") (class "Default")
      (node (ref "D40TOP") (pin "16") (pinfunction "1_16") (pintype "passive"))
      (node (ref "E40") (pin "29") (pinfunction "29_29") (pintype "passive"))
      (node (ref "T35") (pin "2") (pinfunction "B_2") (pintype "passive"))
    )
    (net (code "51") (name "MB5") (class "Default")
      (node (ref "D40BOT") (pin "17") (pinfunction "1_17") (pintype "passive"))
      (node (ref "E40") (pin "30") (pinfunction "30_30") (pintype "passive"))
      (node (ref "T36") (pin "2") (pinfunction "B_2") (pintype "passive"))
    )
    (net (code "52") (name "MB6") (class "Default")
      (node (ref "E40TOP") (pin "3") (pinfunction "1_3") (pintype "passive"))
      (node (ref "F40") (pin "5") (pinfunction "5_5") (pintype "passive"))
      (node (ref "T37") (pin "2") (pinfunction "B_2") (pintype "passive"))
    )
    (net (code "53") (name "MB7") (class "Default")
      (node (ref "E40BOT") (pin "3") (pinfunction "1_3") (pintype "passive"))
      (node (ref "F40") (pin "6") (pinfunction "6_6") (pintype "passive"))
      (node (ref "T38") (pin "2") (pinfunction "B_2") (pintype "passive"))
    )
    (net (code "54") (name "MB8") (class "Default")
      (node (ref "E40TOP") (pin "8") (pinfunction "1_8") (pintype "passive"))
      (node (ref "F40") (pin "15") (pinfunction "15_15") (pintype "passive"))
      (node (ref "T39") (pin "2") (pinfunction "B_2") (pintype "passive"))
    )
    (net (code "55") (name "MB9") (class "Default")
      (node (ref "E40BOT") (pin "11") (pinfunction "1_11") (pintype "passive"))
      (node (ref "F40") (pin "16") (pinfunction "16_16") (pintype "passive"))
      (node (ref "T40") (pin "2") (pinfunction "B_2") (pintype "passive"))
    )
    (net (code "56") (name "MB10") (class "Default")
      (node (ref "E40TOP") (pin "16") (pinfunction "1_16") (pintype "passive"))
      (node (ref "F40") (pin "29") (pinfunction "29_29") (pintype "passive"))
      (node (ref "T41") (pin "2") (pinfunction "B_2") (pintype "passive"))
    )
    (net (code "57") (name "MB11") (class "Default")
      (node (ref "E40BOT") (pin "17") (pinfunction "1_17") (pintype "passive"))
      (node (ref "F40") (pin "30") (pinfunction "30_30") (pintype "passive"))
      (node (ref "T42") (pin "2") (pinfunction "B_2") (pintype "passive"))
    )
    (net (code "58") (name "MQ0") (class "Default")
      (node (ref "D40TOP") (pin "5") (pinfunction "1_5") (pintype "passive"))
      (node (ref "E40") (pin "9") (pinfunction "9_9") (pintype "passive"))
      (node (ref "T55") (pin "2") (pinfunction "B_2") (pintype "passive"))
    )
    (net (code "59") (name "MQ1") (class "Default")
      (node (ref "D40BOT") (pin "1") (pinfunction "1_1") (pintype "passive"))
      (node (ref "E40") (pin "2") (pinfunction "2_2") (pintype "passive"))
      (node (ref "T56") (pin "2") (pinfunction "B_2") (pintype "passive"))
    )
    (net (code "60") (name "MQ2") (class "Default")
      (node (ref "D40TOP") (pin "13") (pinfunction "1_13") (pintype "passive"))
      (node (ref "E40") (pin "23") (pinfunction "23_23") (pintype "passive"))
      (node (ref "T57") (pin "2") (pinfunction "B_2") (pintype "passive"))
    )
    (net (code "61") (name "MQ3") (class "Default")
      (node (ref "D40BOT") (pin "6") (pinfunction "1_6") (pintype "passive"))
      (node (ref "E40") (pin "12") (pinfunction "12_12") (pintype "passive"))
      (node (ref "T58") (pin "2") (pinfunction "B_2") (pintype "passive"))
    )
    (net (code "62") (name "MQ4") (class "Default")
      (node (ref "D40TOP") (pin "18") (pinfunction "1_18") (pintype "passive"))
      (node (ref "E40") (pin "33") (pinfunction "33_33") (pintype "passive"))
      (node (ref "T59") (pin "2") (pinfunction "B_2") (pintype "passive"))
    )
    (net (code "63") (name "MQ5") (class "Default")
      (node (ref "D40BOT") (pin "15") (pinfunction "1_15") (pintype "passive"))
      (node (ref "E40") (pin "26") (pinfunction "26_26") (pintype "passive"))
      (node (ref "T60") (pin "2") (pinfunction "B_2") (pintype "passive"))
    )
    (net (code "64") (name "MQ6") (class "Default")
      (node (ref "E40TOP") (pin "5") (pinfunction "1_5") (pintype "passive"))
      (node (ref "F40") (pin "9") (pinfunction "9_9") (pintype "passive"))
      (node (ref "T61") (pin "2") (pinfunction "B_2") (pintype "passive"))
    )
    (net (code "65") (name "MQ7") (class "Default")
      (node (ref "E40BOT") (pin "1") (pinfunction "1_1") (pintype "passive"))
      (node (ref "F40") (pin "2") (pinfunction "2_2") (pintype "passive"))
      (node (ref "T62") (pin "2") (pinfunction "B_2") (pintype "passive"))
    )
    (net (code "66") (name "MQ8") (class "Default")
      (node (ref "E40TOP") (pin "13") (pinfunction "1_13") (pintype "passive"))
      (node (ref "F40") (pin "23") (pinfunction "23_23") (pintype "passive"))
      (node (ref "T63") (pin "2") (pinfunction "B_2") (pintype "passive"))
    )
    (net (code "67") (name "MQ9") (class "Default")
      (node (ref "E40BOT") (pin "6") (pinfunction "1_6") (pintype "passive"))
      (node (ref "F40") (pin "12") (pinfunction "12_12") (pintype "passive"))
      (node (ref "T64") (pin "2") (pinfunction "B_2") (pintype "passive"))
    )
    (net (code "68") (name "MQ10") (class "Default")
      (node (ref "E40TOP") (pin "18") (pinfunction "1_18") (pintype "passive"))
      (node (ref "F40") (pin "33") (pinfunction "33_33") (pintype "passive"))
      (node (ref "T65") (pin "2") (pinfunction "B_2") (pintype "passive"))
    )
    (net (code "69") (name "MQ11") (class "Default")
      (node (ref "E40BOT") (pin "15") (pinfunction "1_15") (pintype "passive"))
      (node (ref "F40") (pin "26") (pinfunction "26_26") (pintype "passive"))
      (node (ref "T66") (pin "2") (pinfunction "B_2") (pintype "passive"))
    )
    (net (code "70") (name "Net-(AC0-PadA)") (class "Default")
      (node (ref "AC0") (pin "A") (pinfunction "A_A") (pintype "passive"))
      (node (ref "R43") (pin "2") (pinfunction "2_2") (pintype "passive"))
    )
    (net (code "71") (name "Net-(AC1-PadA)") (class "Default")
      (node (ref "AC1") (pin "A") (pinfunction "A_A") (pintype "passive"))
      (node (ref "R44") (pin "2") (pinfunction "2_2") (pintype "passive"))
    )
    (net (code "72") (name "Net-(AC2-PadA)") (class "Default")
      (node (ref "AC2") (pin "A") (pinfunction "A_A") (pintype "passive"))
      (node (ref "R45") (pin "2") (pinfunction "2_2") (pintype "passive"))
    )
    (net (code "73") (name "Net-(AC3-PadA)") (class "Default")
      (node (ref "AC3") (pin "A") (pinfunction "A_A") (pintype "passive"))
      (node (ref "R46") (pin "2") (pinfunction "2_2") (pintype "passive"))
    )
    (net (code "74") (name "Net-(AC4-PadA)") (class "Default")
      (node (ref "AC4") (pin "A") (pinfunction "A_A") (pintype "passive"))
      (node (ref "R47") (pin "2") (pinfunction "2_2") (pintype "passive"))
    )
    (net (code "75") (name "Net-(AC5-PadA)") (class "Default")
      (node (ref "AC5") (pin "A") (pinfunction "A_A") (pintype "passive"))
      (node (ref "R48") (pin "2") (pinfunction "2_2") (pintype "passive"))
    )
    (net (code "76") (name "Net-(AC6-PadA)") (class "Default")
      (node (ref "AC6") (pin "A") (pinfunction "A_A") (pintype "passive"))
      (node (ref "R49") (pin "2") (pinfunction "2_2") (pintype "passive"))
    )
    (net (code "77") (name "Net-(AC7-PadA)") (class "Default")
      (node (ref "AC7") (pin "A") (pinfunction "A_A") (pintype "passive"))
      (node (ref "R50") (pin "2") (pinfunction "2_2") (pintype "passive"))
    )
    (net (code "78") (name "Net-(AC8-PadA)") (class "Default")
      (node (ref "AC8") (pin "A") (pinfunction "A_A") (pintype "passive"))
      (node (ref "R51") (pin "2") (pinfunction "2_2") (pintype "passive"))
    )
    (net (code "79") (name "Net-(AC9-PadA)") (class "Default")
      (node (ref "AC9") (pin "A") (pinfunction "A_A") (pintype "passive"))
      (node (ref "R52") (pin "2") (pinfunction "2_2") (pintype "passive"))
    )
    (net (code "80") (name "Net-(AC10-PadA)") (class "Default")
      (node (ref "AC10") (pin "A") (pinfunction "A_A") (pintype "passive"))
      (node (ref "R53") (pin "2") (pinfunction "2_2") (pintype "passive"))
    )
    (net (code "81") (name "Net-(AC11-PadA)") (class "Default")
      (node (ref "AC11") (pin "A") (pinfunction "A_A") (pintype "passive"))
      (node (ref "R54") (pin "2") (pinfunction "2_2") (pintype "passive"))
    )
    (net (code "82") (name "Net-(AND-PadA)") (class "Default")
      (node (ref "AND") (pin "A") (pinfunction "A_A") (pintype "passive"))
      (node (ref "R82") (pin "2") (pinfunction "2_2") (pintype "passive"))
    )
    (net (code "83") (name "Net-(BREAK-PadA)") (class "Default")
      (node (ref "BREAK") (pin "A") (pinfunction "A_A") (pintype "passive"))
      (node (ref "R81") (pin "2") (pinfunction "2_2") (pintype "passive"))
    )
    (net (code "84") (name "Net-(CURRENTADDRESS-PadA)") (class "Default")
      (node (ref "CURRENTADDRESS") (pin "A") (pinfunction "A_A") (pintype "passive"))
      (node (ref "R80") (pin "2") (pinfunction "2_2") (pintype "passive"))
    )
    (net (code "85") (name "Net-(DCA-PadA)") (class "Default")
      (node (ref "DCA") (pin "A") (pinfunction "A_A") (pintype "passive"))
      (node (ref "R85") (pin "2") (pinfunction "2_2") (pintype "passive"))
    )
    (net (code "86") (name "Net-(DEFER-PadA)") (class "Default")
      (node (ref "DEFER") (pin "A") (pinfunction "A_A") (pintype "passive"))
      (node (ref "R78") (pin "2") (pinfunction "2_2") (pintype "passive"))
    )
    (net (code "87") (name "Net-(DF0-PadA)") (class "Default")
      (node (ref "DF0") (pin "A") (pinfunction "A_A") (pintype "passive"))
      (node (ref "R1") (pin "2") (pinfunction "2_2") (pintype "passive"))
    )
    (net (code "88") (name "Net-(DF1-PadA)") (class "Default")
      (node (ref "DF1") (pin "A") (pinfunction "A_A") (pintype "passive"))
      (node (ref "R2") (pin "2") (pinfunction "2_2") (pintype "passive"))
    )
    (net (code "89") (name "Net-(DF2-PadA)") (class "Default")
      (node (ref "DF2") (pin "A") (pinfunction "A_A") (pintype "passive"))
      (node (ref "R3") (pin "2") (pinfunction "2_2") (pintype "passive"))
    )
    (net (code "90") (name "Net-(EXECUTE-PadA)") (class "Default")
      (node (ref "EXECUTE") (pin "A") (pinfunction "A_A") (pintype "passive"))
      (node (ref "R77") (pin "2") (pinfunction "2_2") (pintype "passive"))
    )
    (net (code "91") (name "Net-(FETCH-PadA)") (class "Default")
      (node (ref "FETCH") (pin "A") (pinfunction "A_A") (pintype "passive"))
      (node (ref "R76") (pin "2") (pinfunction "2_2") (pintype "passive"))
    )
    (net (code "92") (name "Net-(IF0-PadA)") (class "Default")
      (node (ref "IF0") (pin "A") (pinfunction "A_A") (pintype "passive"))
      (node (ref "R4") (pin "2") (pinfunction "2_2") (pintype "passive"))
    )
    (net (code "93") (name "Net-(IF1-PadA)") (class "Default")
      (node (ref "IF1") (pin "A") (pinfunction "A_A") (pintype "passive"))
      (node (ref "R5") (pin "2") (pinfunction "2_2") (pintype "passive"))
    )
    (net (code "94") (name "Net-(IF2-PadA)") (class "Default")
      (node (ref "IF2") (pin "A") (pinfunction "A_A") (pintype "passive"))
      (node (ref "R6") (pin "2") (pinfunction "2_2") (pintype "passive"))
    )
    (net (code "95") (name "Net-(ION-PadA)") (class "Default")
      (node (ref "ION") (pin "A") (pinfunction "A_A") (pintype "passive"))
      (node (ref "R73") (pin "2") (pinfunction "2_2") (pintype "passive"))
    )
    (net (code "96") (name "Net-(IOT-PadA)") (class "Default")
      (node (ref "IOT") (pin "A") (pinfunction "A_A") (pintype "passive"))
      (node (ref "R88") (pin "2") (pinfunction "2_2") (pintype "passive"))
    )
    (net (code "97") (name "Net-(ISZ-PadA)") (class "Default")
      (node (ref "ISZ") (pin "A") (pinfunction "A_A") (pintype "passive"))
      (node (ref "R84") (pin "2") (pinfunction "2_2") (pintype "passive"))
    )
    (net (code "98") (name "Net-(JMP-PadA)") (class "Default")
      (node (ref "JMP") (pin "A") (pinfunction "A_A") (pintype "passive"))
      (node (ref "R87") (pin "2") (pinfunction "2_2") (pintype "passive"))
    )
    (net (code "99") (name "Net-(JMS-PadA)") (class "Default")
      (node (ref "JMS") (pin "A") (pinfunction "A_A") (pintype "passive"))
      (node (ref "R86") (pin "2") (pinfunction "2_2") (pintype "passive"))
    )
    (net (code "100") (name "Net-(LINK-PadA)") (class "Default")
      (node (ref "LINK") (pin "A") (pinfunction "A_A") (pintype "passive"))
      (node (ref "R72") (pin "2") (pinfunction "2_2") (pintype "passive"))
    )
    (net (code "101") (name "Net-(MA0-PadA)") (class "Default")
      (node (ref "MA0") (pin "A") (pinfunction "A_A") (pintype "passive"))
      (node (ref "R19") (pin "2") (pinfunction "2_2") (pintype "passive"))
    )
    (net (code "102") (name "Net-(MA1-PadA)") (class "Default")
      (node (ref "MA1") (pin "A") (pinfunction "A_A") (pintype "passive"))
      (node (ref "R20") (pin "2") (pinfunction "2_2") (pintype "passive"))
    )
    (net (code "103") (name "Net-(MA2-PadA)") (class "Default")
      (node (ref "MA2") (pin "A") (pinfunction "A_A") (pintype "passive"))
      (node (ref "R21") (pin "2") (pinfunction "2_2") (pintype "passive"))
    )
    (net (code "104") (name "Net-(MA3-PadA)") (class "Default")
      (node (ref "MA3") (pin "A") (pinfunction "A_A") (pintype "passive"))
      (node (ref "R22") (pin "2") (pinfunction "2_2") (pintype "passive"))
    )
    (net (code "105") (name "Net-(MA4-PadA)") (class "Default")
      (node (ref "MA4") (pin "A") (pinfunction "A_A") (pintype "passive"))
      (node (ref "R23") (pin "2") (pinfunction "2_2") (pintype "passive"))
    )
    (net (code "106") (name "Net-(MA5-PadA)") (class "Default")
      (node (ref "MA5") (pin "A") (pinfunction "A_A") (pintype "passive"))
      (node (ref "R24") (pin "2") (pinfunction "2_2") (pintype "passive"))
    )
    (net (code "107") (name "Net-(MA6-PadA)") (class "Default")
      (node (ref "MA6") (pin "A") (pinfunction "A_A") (pintype "passive"))
      (node (ref "R25") (pin "2") (pinfunction "2_2") (pintype "passive"))
    )
    (net (code "108") (name "Net-(MA7-PadA)") (class "Default")
      (node (ref "MA7") (pin "A") (pinfunction "A_A") (pintype "passive"))
      (node (ref "R26") (pin "2") (pinfunction "2_2") (pintype "passive"))
    )
    (net (code "109") (name "Net-(MA8-PadA)") (class "Default")
      (node (ref "MA8") (pin "A") (pinfunction "A_A") (pintype "passive"))
      (node (ref "R27") (pin "2") (pinfunction "2_2") (pintype "passive"))
    )
    (net (code "110") (name "Net-(MA9-PadA)") (class "Default")
      (node (ref "MA9") (pin "A") (pinfunction "A_A") (pintype "passive"))
      (node (ref "R28") (pin "2") (pinfunction "2_2") (pintype "passive"))
    )
    (net (code "111") (name "Net-(MA10-PadA)") (class "Default")
      (node (ref "MA10") (pin "A") (pinfunction "A_A") (pintype "passive"))
      (node (ref "R29") (pin "2") (pinfunction "2_2") (pintype "passive"))
    )
    (net (code "112") (name "Net-(MA11-PadA)") (class "Default")
      (node (ref "MA11") (pin "A") (pinfunction "A_A") (pintype "passive"))
      (node (ref "R30") (pin "2") (pinfunction "2_2") (pintype "passive"))
    )
    (net (code "113") (name "Net-(MB0-PadA)") (class "Default")
      (node (ref "MB0") (pin "A") (pinfunction "A_A") (pintype "passive"))
      (node (ref "R31") (pin "2") (pinfunction "2_2") (pintype "passive"))
    )
    (net (code "114") (name "Net-(MB1-PadA)") (class "Default")
      (node (ref "MB1") (pin "A") (pinfunction "A_A") (pintype "passive"))
      (node (ref "R32") (pin "2") (pinfunction "2_2") (pintype "passive"))
    )
    (net (code "115") (name "Net-(MB2-PadA)") (class "Default")
      (node (ref "MB2") (pin "A") (pinfunction "A_A") (pintype "passive"))
      (node (ref "R33") (pin "2") (pinfunction "2_2") (pintype "passive"))
    )
    (net (code "116") (name "Net-(MB3-PadA)") (class "Default")
      (node (ref "MB3") (pin "A") (pinfunction "A_A") (pintype "passive"))
      (node (ref "R34") (pin "2") (pinfunction "2_2") (pintype "passive"))
    )
    (net (code "117") (name "Net-(MB4-PadA)") (class "Default")
      (node (ref "MB4") (pin "A") (pinfunction "A_A") (pintype "passive"))
      (node (ref "R35") (pin "2") (pinfunction "2_2") (pintype "passive"))
    )
    (net (code "118") (name "Net-(MB5-PadA)") (class "Default")
      (node (ref "MB5") (pin "A") (pinfunction "A_A") (pintype "passive"))
      (node (ref "R36") (pin "2") (pinfunction "2_2") (pintype "passive"))
    )
    (net (code "119") (name "Net-(MB6-PadA)") (class "Default")
      (node (ref "MB6") (pin "A") (pinfunction "A_A") (pintype "passive"))
      (node (ref "R37") (pin "2") (pinfunction "2_2") (pintype "passive"))
    )
    (net (code "120") (name "Net-(MB7-PadA)") (class "Default")
      (node (ref "MB7") (pin "A") (pinfunction "A_A") (pintype "passive"))
      (node (ref "R38") (pin "2") (pinfunction "2_2") (pintype "passive"))
    )
    (net (code "121") (name "Net-(MB8-PadA)") (class "Default")
      (node (ref "MB8") (pin "A") (pinfunction "A_A") (pintype "passive"))
      (node (ref "R39") (pin "2") (pinfunction "2_2") (pintype "passive"))
    )
    (net (code "122") (name "Net-(MB9-PadA)") (class "Default")
      (node (ref "MB9") (pin "A") (pinfunction "A_A") (pintype "passive"))
      (node (ref "R40") (pin "2") (pinfunction "2_2") (pintype "passive"))
    )
    (net (code "123") (name "Net-(MB10-PadA)") (class "Default")
      (node (ref "MB10") (pin "A") (pinfunction "A_A") (pintype "passive"))
      (node (ref "R41") (pin "2") (pinfunction "2_2") (pintype "passive"))
    )
    (net (code "124") (name "Net-(MB11-PadA)") (class "Default")
      (node (ref "MB11") (pin "A") (pinfunction "A_A") (pintype "passive"))
      (node (ref "R42") (pin "2") (pinfunction "2_2") (pintype "passive"))
    )
    (net (code "125") (name "Net-(MQ0-PadA)") (class "Default")
      (node (ref "MQ0") (pin "A") (pinfunction "A_A") (pintype "passive"))
      (node (ref "R55") (pin "2") (pinfunction "2_2") (pintype "passive"))
    )
    (net (code "126") (name "Net-(MQ1-PadA)") (class "Default")
      (node (ref "MQ1") (pin "A") (pinfunction "A_A") (pintype "passive"))
      (node (ref "R56") (pin "2") (pinfunction "2_2") (pintype "passive"))
    )
    (net (code "127") (name "Net-(MQ2-PadA)") (class "Default")
      (node (ref "MQ2") (pin "A") (pinfunction "A_A") (pintype "passive"))
      (node (ref "R57") (pin "2") (pinfunction "2_2") (pintype "passive"))
    )
    (net (code "128") (name "Net-(MQ3-PadA)") (class "Default")
      (node (ref "MQ3") (pin "A") (pinfunction "A_A") (pintype "passive"))
      (node (ref "R58") (pin "2") (pinfunction "2_2") (pintype "passive"))
    )
    (net (code "129") (name "Net-(MQ4-PadA)") (class "Default")
      (node (ref "MQ4") (pin "A") (pinfunction "A_A") (pintype "passive"))
      (node (ref "R59") (pin "2") (pinfunction "2_2") (pintype "passive"))
    )
    (net (code "130") (name "Net-(MQ5-PadA)") (class "Default")
      (node (ref "MQ5") (pin "A") (pinfunction "A_A") (pintype "passive"))
      (node (ref "R60") (pin "2") (pinfunction "2_2") (pintype "passive"))
    )
    (net (code "131") (name "Net-(MQ6-PadA)") (class "Default")
      (node (ref "MQ6") (pin "A") (pinfunction "A_A") (pintype "passive"))
      (node (ref "R61") (pin "2") (pinfunction "2_2") (pintype "passive"))
    )
    (net (code "132") (name "Net-(MQ7-PadA)") (class "Default")
      (node (ref "MQ7") (pin "A") (pinfunction "A_A") (pintype "passive"))
      (node (ref "R62") (pin "2") (pinfunction "2_2") (pintype "passive"))
    )
    (net (code "133") (name "Net-(MQ8-PadA)") (class "Default")
      (node (ref "MQ8") (pin "A") (pinfunction "A_A") (pintype "passive"))
      (node (ref "R63") (pin "2") (pinfunction "2_2") (pintype "passive"))
    )
    (net (code "134") (name "Net-(MQ9-PadA)") (class "Default")
      (node (ref "MQ9") (pin "A") (pinfunction "A_A") (pintype "passive"))
      (node (ref "R64") (pin "2") (pinfunction "2_2") (pintype "passive"))
    )
    (net (code "135") (name "Net-(MQ10-PadA)") (class "Default")
      (node (ref "MQ10") (pin "A") (pinfunction "A_A") (pintype "passive"))
      (node (ref "R65") (pin "2") (pinfunction "2_2") (pintype "passive"))
    )
    (net (code "136") (name "Net-(MQ11-PadA)") (class "Default")
      (node (ref "MQ11") (pin "A") (pinfunction "A_A") (pintype "passive"))
      (node (ref "R66") (pin "2") (pinfunction "2_2") (pintype "passive"))
    )
    (net (code "137") (name "Net-(OPR-PadA)") (class "Default")
      (node (ref "OPR") (pin "A") (pinfunction "A_A") (pintype "passive"))
      (node (ref "R89") (pin "2") (pinfunction "2_2") (pintype "passive"))
    )
    (net (code "138") (name "Net-(PAUSE-PadA)") (class "Default")
      (node (ref "PAUSE") (pin "A") (pinfunction "A_A") (pintype "passive"))
      (node (ref "R74") (pin "2") (pinfunction "2_2") (pintype "passive"))
    )
    (net (code "139") (name "Net-(PC0-PadA)") (class "Default")
      (node (ref "PC0") (pin "A") (pinfunction "A_A") (pintype "passive"))
      (node (ref "R7") (pin "2") (pinfunction "2_2") (pintype "passive"))
    )
    (net (code "140") (name "Net-(PC1-PadA)") (class "Default")
      (node (ref "PC1") (pin "A") (pinfunction "A_A") (pintype "passive"))
      (node (ref "R8") (pin "2") (pinfunction "2_2") (pintype "passive"))
    )
    (net (code "141") (name "Net-(PC2-PadA)") (class "Default")
      (node (ref "PC2") (pin "A") (pinfunction "A_A") (pintype "passive"))
      (node (ref "R9") (pin "2") (pinfunction "2_2") (pintype "passive"))
    )
    (net (code "142") (name "Net-(PC3-PadA)") (class "Default")
      (node (ref "PC3") (pin "A") (pinfunction "A_A") (pintype "passive"))
      (node (ref "R10") (pin "2") (pinfunction "2_2") (pintype "passive"))
    )
    (net (code "143") (name "Net-(PC4-PadA)") (class "Default")
      (node (ref "PC4") (pin "A") (pinfunction "A_A") (pintype "passive"))
      (node (ref "R11") (pin "2") (pinfunction "2_2") (pintype "passive"))
    )
    (net (code "144") (name "Net-(PC5-PadA)") (class "Default")
      (node (ref "PC5") (pin "A") (pinfunction "A_A") (pintype "passive"))
      (node (ref "R12") (pin "2") (pinfunction "2_2") (pintype "passive"))
    )
    (net (code "145") (name "Net-(PC6-PadA)") (class "Default")
      (node (ref "PC6") (pin "A") (pinfunction "A_A") (pintype "passive"))
      (node (ref "R13") (pin "2") (pinfunction "2_2") (pintype "passive"))
    )
    (net (code "146") (name "Net-(PC7-PadA)") (class "Default")
      (node (ref "PC7") (pin "A") (pinfunction "A_A") (pintype "passive"))
      (node (ref "R14") (pin "2") (pinfunction "2_2") (pintype "passive"))
    )
    (net (code "147") (name "Net-(PC8-PadA)") (class "Default")
      (node (ref "PC8") (pin "A") (pinfunction "A_A") (pintype "passive"))
      (node (ref "R15") (pin "2") (pinfunction "2_2") (pintype "passive"))
    )
    (net (code "148") (name "Net-(PC9-PadA)") (class "Default")
      (node (ref "PC9") (pin "A") (pinfunction "A_A") (pintype "passive"))
      (node (ref "R16") (pin "2") (pinfunction "2_2") (pintype "passive"))
    )
    (net (code "149") (name "Net-(PC10-PadA)") (class "Default")
      (node (ref "PC10") (pin "A") (pinfunction "A_A") (pintype "passive"))
      (node (ref "R17") (pin "2") (pinfunction "2_2") (pintype "passive"))
    )
    (net (code "150") (name "Net-(PC11-PadA)") (class "Default")
      (node (ref "PC11") (pin "A") (pinfunction "A_A") (pintype "passive"))
      (node (ref "R18") (pin "2") (pinfunction "2_2") (pintype "passive"))
    )
    (net (code "151") (name "Net-(R67-Pad2)") (class "Default")
      (node (ref "R67") (pin "2") (pinfunction "2_2") (pintype "passive"))
      (node (ref "SC0") (pin "A") (pinfunction "A_A") (pintype "passive"))
    )
    (net (code "152") (name "Net-(R68-Pad2)") (class "Default")
      (node (ref "R68") (pin "2") (pinfunction "2_2") (pintype "passive"))
      (node (ref "SC1") (pin "A") (pinfunction "A_A") (pintype "passive"))
    )
    (net (code "153") (name "Net-(R69-Pad2)") (class "Default")
      (node (ref "R69") (pin "2") (pinfunction "2_2") (pintype "passive"))
      (node (ref "SC2") (pin "A") (pinfunction "A_A") (pintype "passive"))
    )
    (net (code "154") (name "Net-(R70-Pad2)") (class "Default")
      (node (ref "R70") (pin "2") (pinfunction "2_2") (pintype "passive"))
      (node (ref "SC3") (pin "A") (pinfunction "A_A") (pintype "passive"))
    )
    (net (code "155") (name "Net-(R71-Pad2)") (class "Default")
      (node (ref "R71") (pin "2") (pinfunction "2_2") (pintype "passive"))
      (node (ref "SC4") (pin "A") (pinfunction "A_A") (pintype "passive"))
    )
    (net (code "156") (name "Net-(R75-Pad2)") (class "Default")
      (node (ref "R75") (pin "2") (pinfunction "2_2") (pintype "passive"))
      (node (ref "RUN") (pin "A") (pinfunction "A_A") (pintype "passive"))
    )
    (net (code "157") (name "Net-(R79-Pad2)") (class "Default")
      (node (ref "R79") (pin "2") (pinfunction "2_2") (pintype "passive"))
      (node (ref "WORDCOUNT") (pin "A") (pinfunction "A_A") (pintype "passive"))
    )
    (net (code "158") (name "Net-(R83-Pad2)") (class "Default")
      (node (ref "R83") (pin "2") (pinfunction "2_2") (pintype "passive"))
      (node (ref "TAD") (pin "A") (pinfunction "A_A") (pintype "passive"))
    )
    (net (code "159") (name "Net-(T1-C)") (class "Default")
      (node (ref "DF0") (pin "B") (pinfunction "B_B") (pintype "passive"))
      (node (ref "T1") (pin "3") (pinfunction "C_3") (pintype "passive"))
    )
    (net (code "160") (name "Net-(T2-C)") (class "Default")
      (node (ref "DF1") (pin "B") (pinfunction "B_B") (pintype "passive"))
      (node (ref "T2") (pin "3") (pinfunction "C_3") (pintype "passive"))
    )
    (net (code "161") (name "Net-(T3-C)") (class "Default")
      (node (ref "DF2") (pin "B") (pinfunction "B_B") (pintype "passive"))
      (node (ref "T3") (pin "3") (pinfunction "C_3") (pintype "passive"))
    )
    (net (code "162") (name "Net-(T4-C)") (class "Default")
      (node (ref "IF0") (pin "B") (pinfunction "B_B") (pintype "passive"))
      (node (ref "T4") (pin "3") (pinfunction "C_3") (pintype "passive"))
    )
    (net (code "163") (name "Net-(T5-C)") (class "Default")
      (node (ref "IF1") (pin "B") (pinfunction "B_B") (pintype "passive"))
      (node (ref "T5") (pin "3") (pinfunction "C_3") (pintype "passive"))
    )
    (net (code "164") (name "Net-(T6-C)") (class "Default")
      (node (ref "IF2") (pin "B") (pinfunction "B_B") (pintype "passive"))
      (node (ref "T6") (pin "3") (pinfunction "C_3") (pintype "passive"))
    )
    (net (code "165") (name "Net-(T7-C)") (class "Default")
      (node (ref "PC0") (pin "B") (pinfunction "B_B") (pintype "passive"))
      (node (ref "T7") (pin "3") (pinfunction "C_3") (pintype "passive"))
    )
    (net (code "166") (name "Net-(T8-C)") (class "Default")
      (node (ref "PC1") (pin "B") (pinfunction "B_B") (pintype "passive"))
      (node (ref "T8") (pin "3") (pinfunction "C_3") (pintype "passive"))
    )
    (net (code "167") (name "Net-(T9-C)") (class "Default")
      (node (ref "PC2") (pin "B") (pinfunction "B_B") (pintype "passive"))
      (node (ref "T9") (pin "3") (pinfunction "C_3") (pintype "passive"))
    )
    (net (code "168") (name "Net-(T10-C)") (class "Default")
      (node (ref "PC3") (pin "B") (pinfunction "B_B") (pintype "passive"))
      (node (ref "T10") (pin "3") (pinfunction "C_3") (pintype "passive"))
    )
    (net (code "169") (name "Net-(T11-C)") (class "Default")
      (node (ref "PC4") (pin "B") (pinfunction "B_B") (pintype "passive"))
      (node (ref "T11") (pin "3") (pinfunction "C_3") (pintype "passive"))
    )
    (net (code "170") (name "Net-(T12-C)") (class "Default")
      (node (ref "PC5") (pin "B") (pinfunction "B_B") (pintype "passive"))
      (node (ref "T12") (pin "3") (pinfunction "C_3") (pintype "passive"))
    )
    (net (code "171") (name "Net-(T13-C)") (class "Default")
      (node (ref "PC6") (pin "B") (pinfunction "B_B") (pintype "passive"))
      (node (ref "T13") (pin "3") (pinfunction "C_3") (pintype "passive"))
    )
    (net (code "172") (name "Net-(T14-C)") (class "Default")
      (node (ref "PC7") (pin "B") (pinfunction "B_B") (pintype "passive"))
      (node (ref "T14") (pin "3") (pinfunction "C_3") (pintype "passive"))
    )
    (net (code "173") (name "Net-(T15-C)") (class "Default")
      (node (ref "PC8") (pin "B") (pinfunction "B_B") (pintype "passive"))
      (node (ref "T15") (pin "3") (pinfunction "C_3") (pintype "passive"))
    )
    (net (code "174") (name "Net-(T16-C)") (class "Default")
      (node (ref "PC9") (pin "B") (pinfunction "B_B") (pintype "passive"))
      (node (ref "T16") (pin "3") (pinfunction "C_3") (pintype "passive"))
    )
    (net (code "175") (name "Net-(T17-C)") (class "Default")
      (node (ref "PC10") (pin "B") (pinfunction "B_B") (pintype "passive"))
      (node (ref "T17") (pin "3") (pinfunction "C_3") (pintype "passive"))
    )
    (net (code "176") (name "Net-(T18-C)") (class "Default")
      (node (ref "PC11") (pin "B") (pinfunction "B_B") (pintype "passive"))
      (node (ref "T18") (pin "3") (pinfunction "C_3") (pintype "passive"))
    )
    (net (code "177") (name "Net-(T19-C)") (class "Default")
      (node (ref "MA0") (pin "B") (pinfunction "B_B") (pintype "passive"))
      (node (ref "T19") (pin "3") (pinfunction "C_3") (pintype "passive"))
    )
    (net (code "178") (name "Net-(T20-C)") (class "Default")
      (node (ref "MA1") (pin "B") (pinfunction "B_B") (pintype "passive"))
      (node (ref "T20") (pin "3") (pinfunction "C_3") (pintype "passive"))
    )
    (net (code "179") (name "Net-(T21-C)") (class "Default")
      (node (ref "MA2") (pin "B") (pinfunction "B_B") (pintype "passive"))
      (node (ref "T21") (pin "3") (pinfunction "C_3") (pintype "passive"))
    )
    (net (code "180") (name "Net-(T22-C)") (class "Default")
      (node (ref "MA3") (pin "B") (pinfunction "B_B") (pintype "passive"))
      (node (ref "T22") (pin "3") (pinfunction "C_3") (pintype "passive"))
    )
    (net (code "181") (name "Net-(T23-C)") (class "Default")
      (node (ref "MA4") (pin "B") (pinfunction "B_B") (pintype "passive"))
      (node (ref "T23") (pin "3") (pinfunction "C_3") (pintype "passive"))
    )
    (net (code "182") (name "Net-(T24-C)") (class "Default")
      (node (ref "MA5") (pin "B") (pinfunction "B_B") (pintype "passive"))
      (node (ref "T24") (pin "3") (pinfunction "C_3") (pintype "passive"))
    )
    (net (code "183") (name "Net-(T25-C)") (class "Default")
      (node (ref "MA6") (pin "B") (pinfunction "B_B") (pintype "passive"))
      (node (ref "T25") (pin "3") (pinfunction "C_3") (pintype "passive"))
    )
    (net (code "184") (name "Net-(T26-C)") (class "Default")
      (node (ref "MA7") (pin "B") (pinfunction "B_B") (pintype "passive"))
      (node (ref "T26") (pin "3") (pinfunction "C_3") (pintype "passive"))
    )
    (net (code "185") (name "Net-(T27-C)") (class "Default")
      (node (ref "MA8") (pin "B") (pinfunction "B_B") (pintype "passive"))
      (node (ref "T27") (pin "3") (pinfunction "C_3") (pintype "passive"))
    )
    (net (code "186") (name "Net-(T28-C)") (class "Default")
      (node (ref "MA9") (pin "B") (pinfunction "B_B") (pintype "passive"))
      (node (ref "T28") (pin "3") (pinfunction "C_3") (pintype "passive"))
    )
    (net (code "187") (name "Net-(T29-C)") (class "Default")
      (node (ref "MA10") (pin "B") (pinfunction "B_B") (pintype "passive"))
      (node (ref "T29") (pin "3") (pinfunction "C_3") (pintype "passive"))
    )
    (net (code "188") (name "Net-(T30-C)") (class "Default")
      (node (ref "MA11") (pin "B") (pinfunction "B_B") (pintype "passive"))
      (node (ref "T30") (pin "3") (pinfunction "C_3") (pintype "passive"))
    )
    (net (code "189") (name "Net-(T31-C)") (class "Default")
      (node (ref "MB0") (pin "B") (pinfunction "B_B") (pintype "passive"))
      (node (ref "T31") (pin "3") (pinfunction "C_3") (pintype "passive"))
    )
    (net (code "190") (name "Net-(T32-C)") (class "Default")
      (node (ref "MB1") (pin "B") (pinfunction "B_B") (pintype "passive"))
      (node (ref "T32") (pin "3") (pinfunction "C_3") (pintype "passive"))
    )
    (net (code "191") (name "Net-(T33-C)") (class "Default")
      (node (ref "MB2") (pin "B") (pinfunction "B_B") (pintype "passive"))
      (node (ref "T33") (pin "3") (pinfunction "C_3") (pintype "passive"))
    )
    (net (code "192") (name "Net-(T34-C)") (class "Default")
      (node (ref "MB3") (pin "B") (pinfunction "B_B") (pintype "passive"))
      (node (ref "T34") (pin "3") (pinfunction "C_3") (pintype "passive"))
    )
    (net (code "193") (name "Net-(T35-C)") (class "Default")
      (node (ref "MB4") (pin "B") (pinfunction "B_B") (pintype "passive"))
      (node (ref "T35") (pin "3") (pinfunction "C_3") (pintype "passive"))
    )
    (net (code "194") (name "Net-(T36-C)") (class "Default")
      (node (ref "MB5") (pin "B") (pinfunction "B_B") (pintype "passive"))
      (node (ref "T36") (pin "3") (pinfunction "C_3") (pintype "passive"))
    )
    (net (code "195") (name "Net-(T37-C)") (class "Default")
      (node (ref "MB6") (pin "B") (pinfunction "B_B") (pintype "passive"))
      (node (ref "T37") (pin "3") (pinfunction "C_3") (pintype "passive"))
    )
    (net (code "196") (name "Net-(T38-C)") (class "Default")
      (node (ref "MB7") (pin "B") (pinfunction "B_B") (pintype "passive"))
      (node (ref "T38") (pin "3") (pinfunction "C_3") (pintype "passive"))
    )
    (net (code "197") (name "Net-(T39-C)") (class "Default")
      (node (ref "MB8") (pin "B") (pinfunction "B_B") (pintype "passive"))
      (node (ref "T39") (pin "3") (pinfunction "C_3") (pintype "passive"))
    )
    (net (code "198") (name "Net-(T40-C)") (class "Default")
      (node (ref "MB9") (pin "B") (pinfunction "B_B") (pintype "passive"))
      (node (ref "T40") (pin "3") (pinfunction "C_3") (pintype "passive"))
    )
    (net (code "199") (name "Net-(T41-C)") (class "Default")
      (node (ref "MB10") (pin "B") (pinfunction "B_B") (pintype "passive"))
      (node (ref "T41") (pin "3") (pinfunction "C_3") (pintype "passive"))
    )
    (net (code "200") (name "Net-(T42-C)") (class "Default")
      (node (ref "MB11") (pin "B") (pinfunction "B_B") (pintype "passive"))
      (node (ref "T42") (pin "3") (pinfunction "C_3") (pintype "passive"))
    )
    (net (code "201") (name "Net-(T43-C)") (class "Default")
      (node (ref "AC0") (pin "B") (pinfunction "B_B") (pintype "passive"))
      (node (ref "T43") (pin "3") (pinfunction "C_3") (pintype "passive"))
    )
    (net (code "202") (name "Net-(T44-C)") (class "Default")
      (node (ref "AC1") (pin "B") (pinfunction "B_B") (pintype "passive"))
      (node (ref "T44") (pin "3") (pinfunction "C_3") (pintype "passive"))
    )
    (net (code "203") (name "Net-(T45-C)") (class "Default")
      (node (ref "AC2") (pin "B") (pinfunction "B_B") (pintype "passive"))
      (node (ref "T45") (pin "3") (pinfunction "C_3") (pintype "passive"))
    )
    (net (code "204") (name "Net-(T46-C)") (class "Default")
      (node (ref "AC3") (pin "B") (pinfunction "B_B") (pintype "passive"))
      (node (ref "T46") (pin "3") (pinfunction "C_3") (pintype "passive"))
    )
    (net (code "205") (name "Net-(T47-C)") (class "Default")
      (node (ref "AC4") (pin "B") (pinfunction "B_B") (pintype "passive"))
      (node (ref "T47") (pin "3") (pinfunction "C_3") (pintype "passive"))
    )
    (net (code "206") (name "Net-(T48-C)") (class "Default")
      (node (ref "AC5") (pin "B") (pinfunction "B_B") (pintype "passive"))
      (node (ref "T48") (pin "3") (pinfunction "C_3") (pintype "passive"))
    )
    (net (code "207") (name "Net-(T49-C)") (class "Default")
      (node (ref "AC6") (pin "B") (pinfunction "B_B") (pintype "passive"))
      (node (ref "T49") (pin "3") (pinfunction "C_3") (pintype "passive"))
    )
    (net (code "208") (name "Net-(T50-C)") (class "Default")
      (node (ref "AC7") (pin "B") (pinfunction "B_B") (pintype "passive"))
      (node (ref "T50") (pin "3") (pinfunction "C_3") (pintype "passive"))
    )
    (net (code "209") (name "Net-(T51-C)") (class "Default")
      (node (ref "AC8") (pin "B") (pinfunction "B_B") (pintype "passive"))
      (node (ref "T51") (pin "3") (pinfunction "C_3") (pintype "passive"))
    )
    (net (code "210") (name "Net-(T52-C)") (class "Default")
      (node (ref "AC9") (pin "B") (pinfunction "B_B") (pintype "passive"))
      (node (ref "T52") (pin "3") (pinfunction "C_3") (pintype "passive"))
    )
    (net (code "211") (name "Net-(T53-C)") (class "Default")
      (node (ref "AC10") (pin "B") (pinfunction "B_B") (pintype "passive"))
      (node (ref "T53") (pin "3") (pinfunction "C_3") (pintype "passive"))
    )
    (net (code "212") (name "Net-(T54-C)") (class "Default")
      (node (ref "AC11") (pin "B") (pinfunction "B_B") (pintype "passive"))
      (node (ref "T54") (pin "3") (pinfunction "C_3") (pintype "passive"))
    )
    (net (code "213") (name "Net-(T55-C)") (class "Default")
      (node (ref "MQ0") (pin "B") (pinfunction "B_B") (pintype "passive"))
      (node (ref "T55") (pin "3") (pinfunction "C_3") (pintype "passive"))
    )
    (net (code "214") (name "Net-(T56-C)") (class "Default")
      (node (ref "MQ1") (pin "B") (pinfunction "B_B") (pintype "passive"))
      (node (ref "T56") (pin "3") (pinfunction "C_3") (pintype "passive"))
    )
    (net (code "215") (name "Net-(T57-C)") (class "Default")
      (node (ref "MQ2") (pin "B") (pinfunction "B_B") (pintype "passive"))
      (node (ref "T57") (pin "3") (pinfunction "C_3") (pintype "passive"))
    )
    (net (code "216") (name "Net-(T58-C)") (class "Default")
      (node (ref "MQ3") (pin "B") (pinfunction "B_B") (pintype "passive"))
      (node (ref "T58") (pin "3") (pinfunction "C_3") (pintype "passive"))
    )
    (net (code "217") (name "Net-(T59-C)") (class "Default")
      (node (ref "MQ4") (pin "B") (pinfunction "B_B") (pintype "passive"))
      (node (ref "T59") (pin "3") (pinfunction "C_3") (pintype "passive"))
    )
    (net (code "218") (name "Net-(T60-C)") (class "Default")
      (node (ref "MQ5") (pin "B") (pinfunction "B_B") (pintype "passive"))
      (node (ref "T60") (pin "3") (pinfunction "C_3") (pintype "passive"))
    )
    (net (code "219") (name "Net-(T61-C)") (class "Default")
      (node (ref "MQ6") (pin "B") (pinfunction "B_B") (pintype "passive"))
      (node (ref "T61") (pin "3") (pinfunction "C_3") (pintype "passive"))
    )
    (net (code "220") (name "Net-(T62-C)") (class "Default")
      (node (ref "MQ7") (pin "B") (pinfunction "B_B") (pintype "passive"))
      (node (ref "T62") (pin "3") (pinfunction "C_3") (pintype "passive"))
    )
    (net (code "221") (name "Net-(T63-C)") (class "Default")
      (node (ref "MQ8") (pin "B") (pinfunction "B_B") (pintype "passive"))
      (node (ref "T63") (pin "3") (pinfunction "C_3") (pintype "passive"))
    )
    (net (code "222") (name "Net-(T64-C)") (class "Default")
      (node (ref "MQ9") (pin "B") (pinfunction "B_B") (pintype "passive"))
      (node (ref "T64") (pin "3") (pinfunction "C_3") (pintype "passive"))
    )
    (net (code "223") (name "Net-(T65-C)") (class "Default")
      (node (ref "MQ10") (pin "B") (pinfunction "B_B") (pintype "passive"))
      (node (ref "T65") (pin "3") (pinfunction "C_3") (pintype "passive"))
    )
    (net (code "224") (name "Net-(T66-C)") (class "Default")
      (node (ref "MQ11") (pin "B") (pinfunction "B_B") (pintype "passive"))
      (node (ref "T66") (pin "3") (pinfunction "C_3") (pintype "passive"))
    )
    (net (code "225") (name "Net-(T67-C)") (class "Default")
      (node (ref "SC0") (pin "B") (pinfunction "B_B") (pintype "passive"))
      (node (ref "T67") (pin "3") (pinfunction "C_3") (pintype "passive"))
    )
    (net (code "226") (name "Net-(T68-C)") (class "Default")
      (node (ref "SC1") (pin "B") (pinfunction "B_B") (pintype "passive"))
      (node (ref "T68") (pin "3") (pinfunction "C_3") (pintype "passive"))
    )
    (net (code "227") (name "Net-(T69-C)") (class "Default")
      (node (ref "SC2") (pin "B") (pinfunction "B_B") (pintype "passive"))
      (node (ref "T69") (pin "3") (pinfunction "C_3") (pintype "passive"))
    )
    (net (code "228") (name "Net-(T70-C)") (class "Default")
      (node (ref "SC3") (pin "B") (pinfunction "B_B") (pintype "passive"))
      (node (ref "T70") (pin "3") (pinfunction "C_3") (pintype "passive"))
    )
    (net (code "229") (name "Net-(T71-C)") (class "Default")
      (node (ref "SC4") (pin "B") (pinfunction "B_B") (pintype "passive"))
      (node (ref "T71") (pin "3") (pinfunction "C_3") (pintype "passive"))
    )
    (net (code "230") (name "Net-(T72-C)") (class "Default")
      (node (ref "LINK") (pin "B") (pinfunction "B_B") (pintype "passive"))
      (node (ref "T72") (pin "3") (pinfunction "C_3") (pintype "passive"))
    )
    (net (code "231") (name "Net-(T73-C)") (class "Default")
      (node (ref "ION") (pin "B") (pinfunction "B_B") (pintype "passive"))
      (node (ref "T73") (pin "3") (pinfunction "C_3") (pintype "passive"))
    )
    (net (code "232") (name "Net-(T74-C)") (class "Default")
      (node (ref "PAUSE") (pin "B") (pinfunction "B_B") (pintype "passive"))
      (node (ref "T74") (pin "3") (pinfunction "C_3") (pintype "passive"))
    )
    (net (code "233") (name "Net-(T75-C)") (class "Default")
      (node (ref "RUN") (pin "B") (pinfunction "B_B") (pintype "passive"))
      (node (ref "T75") (pin "3") (pinfunction "C_3") (pintype "passive"))
    )
    (net (code "234") (name "Net-(T76-C)") (class "Default")
      (node (ref "FETCH") (pin "B") (pinfunction "B_B") (pintype "passive"))
      (node (ref "T76") (pin "3") (pinfunction "C_3") (pintype "passive"))
    )
    (net (code "235") (name "Net-(T77-C)") (class "Default")
      (node (ref "EXECUTE") (pin "B") (pinfunction "B_B") (pintype "passive"))
      (node (ref "T77") (pin "3") (pinfunction "C_3") (pintype "passive"))
    )
    (net (code "236") (name "Net-(T78-C)") (class "Default")
      (node (ref "DEFER") (pin "B") (pinfunction "B_B") (pintype "passive"))
      (node (ref "T78") (pin "3") (pinfunction "C_3") (pintype "passive"))
    )
    (net (code "237") (name "Net-(T79-C)") (class "Default")
      (node (ref "T79") (pin "3") (pinfunction "C_3") (pintype "passive"))
      (node (ref "WORDCOUNT") (pin "B") (pinfunction "B_B") (pintype "passive"))
    )
    (net (code "238") (name "Net-(T80-C)") (class "Default")
      (node (ref "CURRENTADDRESS") (pin "B") (pinfunction "B_B") (pintype "passive"))
      (node (ref "T80") (pin "3") (pinfunction "C_3") (pintype "passive"))
    )
    (net (code "239") (name "Net-(T81-C)") (class "Default")
      (node (ref "BREAK") (pin "B") (pinfunction "B_B") (pintype "passive"))
      (node (ref "T81") (pin "3") (pinfunction "C_3") (pintype "passive"))
    )
    (net (code "240") (name "Net-(T82-C)") (class "Default")
      (node (ref "AND") (pin "B") (pinfunction "B_B") (pintype "passive"))
      (node (ref "T82") (pin "3") (pinfunction "C_3") (pintype "passive"))
    )
    (net (code "241") (name "Net-(T83-C)") (class "Default")
      (node (ref "T83") (pin "3") (pinfunction "C_3") (pintype "passive"))
      (node (ref "TAD") (pin "B") (pinfunction "B_B") (pintype "passive"))
    )
    (net (code "242") (name "Net-(T84-C)") (class "Default")
      (node (ref "ISZ") (pin "B") (pinfunction "B_B") (pintype "passive"))
      (node (ref "T84") (pin "3") (pinfunction "C_3") (pintype "passive"))
    )
    (net (code "243") (name "Net-(T85-C)") (class "Default")
      (node (ref "DCA") (pin "B") (pinfunction "B_B") (pintype "passive"))
      (node (ref "T85") (pin "3") (pinfunction "C_3") (pintype "passive"))
    )
    (net (code "244") (name "Net-(T86-C)") (class "Default")
      (node (ref "JMS") (pin "B") (pinfunction "B_B") (pintype "passive"))
      (node (ref "T86") (pin "3") (pinfunction "C_3") (pintype "passive"))
    )
    (net (code "245") (name "Net-(T87-C)") (class "Default")
      (node (ref "JMP") (pin "B") (pinfunction "B_B") (pintype "passive"))
      (node (ref "T87") (pin "3") (pinfunction "C_3") (pintype "passive"))
    )
    (net (code "246") (name "Net-(T88-C)") (class "Default")
      (node (ref "IOT") (pin "B") (pinfunction "B_B") (pintype "passive"))
      (node (ref "T88") (pin "3") (pinfunction "C_3") (pintype "passive"))
    )
    (net (code "247") (name "Net-(T89-C)") (class "Default")
      (node (ref "OPR") (pin "B") (pinfunction "B_B") (pintype "passive"))
      (node (ref "T89") (pin "3") (pinfunction "C_3") (pintype "passive"))
    )
    (net (code "248") (name "OPR") (class "Default")
      (node (ref "D40") (pin "16") (pinfunction "16_16") (pintype "passive"))
      (node (ref "F40BOT") (pin "11") (pinfunction "1_11") (pintype "passive"))
      (node (ref "T89") (pin "2") (pinfunction "B_2") (pintype "passive"))
    )
    (net (code "249") (name "PAUSE") (class "Default")
      (node (ref "D40") (pin "31") (pinfunction "31_31") (pintype "passive"))
      (node (ref "F40TOP") (pin "17") (pinfunction "1_17") (pintype "passive"))
      (node (ref "T74") (pin "2") (pinfunction "B_2") (pintype "passive"))
    )
    (net (code "250") (name "PC0") (class "Default")
      (node (ref "D40TOP") (pin "1") (pinfunction "1_1") (pintype "passive"))
      (node (ref "E40") (pin "1") (pinfunction "1_1") (pintype "passive"))
      (node (ref "T7") (pin "2") (pinfunction "B_2") (pintype "passive"))
    )
    (net (code "251") (name "PC1") (class "Default")
      (node (ref "D40BOT") (pin "5") (pinfunction "1_5") (pintype "passive"))
      (node (ref "E40") (pin "10") (pinfunction "10_10") (pintype "passive"))
      (node (ref "T8") (pin "2") (pinfunction "B_2") (pintype "passive"))
    )
    (net (code "252") (name "PC2") (class "Default")
      (node (ref "D40TOP") (pin "6") (pinfunction "1_6") (pintype "passive"))
      (node (ref "E40") (pin "11") (pinfunction "11_11") (pintype "passive"))
      (node (ref "T9") (pin "2") (pinfunction "B_2") (pintype "passive"))
    )
    (net (code "253") (name "PC3") (class "Default")
      (node (ref "D40BOT") (pin "14") (pinfunction "1_14") (pintype "passive"))
      (node (ref "E40") (pin "24") (pinfunction "24_24") (pintype "passive"))
      (node (ref "T10") (pin "2") (pinfunction "B_2") (pintype "passive"))
    )
    (net (code "254") (name "PC4") (class "Default")
      (node (ref "D40TOP") (pin "14") (pinfunction "1_14") (pintype "passive"))
      (node (ref "E40") (pin "25") (pinfunction "25_25") (pintype "passive"))
      (node (ref "T11") (pin "2") (pinfunction "B_2") (pintype "passive"))
    )
    (net (code "255") (name "PC5") (class "Default")
      (node (ref "D40BOT") (pin "19") (pinfunction "1_19") (pintype "passive"))
      (node (ref "E40") (pin "34") (pinfunction "34_34") (pintype "passive"))
      (node (ref "T12") (pin "2") (pinfunction "B_2") (pintype "passive"))
    )
    (net (code "256") (name "PC6") (class "Default")
      (node (ref "E40TOP") (pin "1") (pinfunction "1_1") (pintype "passive"))
      (node (ref "F40") (pin "1") (pinfunction "1_1") (pintype "passive"))
      (node (ref "T13") (pin "2") (pinfunction "B_2") (pintype "passive"))
    )
    (net (code "257") (name "PC7") (class "Default")
      (node (ref "E40BOT") (pin "5") (pinfunction "1_5") (pintype "passive"))
      (node (ref "F40") (pin "10") (pinfunction "10_10") (pintype "passive"))
      (node (ref "T14") (pin "2") (pinfunction "B_2") (pintype "passive"))
    )
    (net (code "258") (name "PC8") (class "Default")
      (node (ref "E40TOP") (pin "6") (pinfunction "1_6") (pintype "passive"))
      (node (ref "F40") (pin "11") (pinfunction "11_11") (pintype "passive"))
      (node (ref "T15") (pin "2") (pinfunction "B_2") (pintype "passive"))
    )
    (net (code "259") (name "PC9") (class "Default")
      (node (ref "E40BOT") (pin "14") (pinfunction "1_14") (pintype "passive"))
      (node (ref "F40") (pin "24") (pinfunction "24_24") (pintype "passive"))
      (node (ref "T16") (pin "2") (pinfunction "B_2") (pintype "passive"))
    )
    (net (code "260") (name "PC10") (class "Default")
      (node (ref "E40TOP") (pin "14") (pinfunction "1_14") (pintype "passive"))
      (node (ref "F40") (pin "25") (pinfunction "25_25") (pintype "passive"))
      (node (ref "T17") (pin "2") (pinfunction "B_2") (pintype "passive"))
    )
    (net (code "261") (name "PC11") (class "Default")
      (node (ref "E40BOT") (pin "19") (pinfunction "1_19") (pintype "passive"))
      (node (ref "F40") (pin "34") (pinfunction "34_34") (pintype "passive"))
      (node (ref "T18") (pin "2") (pinfunction "B_2") (pintype "passive"))
    )
    (net (code "262") (name "RUN") (class "Default")
      (node (ref "D40") (pin "33") (pinfunction "33_33") (pintype "passive"))
      (node (ref "F40TOP") (pin "18") (pinfunction "1_18") (pintype "passive"))
      (node (ref "T75") (pin "2") (pinfunction "B_2") (pintype "passive"))
    )
    (net (code "263") (name "SC0") (class "Default")
      (node (ref "C40") (pin "9") (pinfunction "9_9") (pintype "passive"))
      (node (ref "C40TOP") (pin "5") (pinfunction "1_5") (pintype "passive"))
      (node (ref "T67") (pin "2") (pinfunction "B_2") (pintype "passive"))
    )
    (net (code "264") (name "SC1") (class "Default")
      (node (ref "C40") (pin "2") (pinfunction "2_2") (pintype "passive"))
      (node (ref "C40BOT") (pin "1") (pinfunction "1_1") (pintype "passive"))
      (node (ref "T68") (pin "2") (pinfunction "B_2") (pintype "passive"))
    )
    (net (code "265") (name "SC2") (class "Default")
      (node (ref "C40") (pin "23") (pinfunction "23_23") (pintype "passive"))
      (node (ref "C40TOP") (pin "13") (pinfunction "1_13") (pintype "passive"))
      (node (ref "T69") (pin "2") (pinfunction "B_2") (pintype "passive"))
    )
    (net (code "266") (name "SC3") (class "Default")
      (node (ref "C40") (pin "12") (pinfunction "12_12") (pintype "passive"))
      (node (ref "C40BOT") (pin "6") (pinfunction "1_6") (pintype "passive"))
      (node (ref "T70") (pin "2") (pinfunction "B_2") (pintype "passive"))
    )
    (net (code "267") (name "SC4") (class "Default")
      (node (ref "C40") (pin "33") (pinfunction "33_33") (pintype "passive"))
      (node (ref "C40TOP") (pin "18") (pinfunction "1_18") (pintype "passive"))
      (node (ref "T71") (pin "2") (pinfunction "B_2") (pintype "passive"))
    )
    (net (code "268") (name "TAD") (class "Default")
      (node (ref "D40") (pin "4") (pinfunction "4_4") (pintype "passive"))
      (node (ref "F40BOT") (pin "2") (pinfunction "1_2") (pintype "passive"))
      (node (ref "T83") (pin "2") (pinfunction "B_2") (pintype "passive"))
    )
    (net (code "269") (name "WC") (class "Default")
      (node (ref "D40") (pin "30") (pinfunction "30_30") (pintype "passive"))
      (node (ref "F40BOT") (pin "17") (pinfunction "1_17") (pintype "passive"))
      (node (ref "T79") (pin "2") (pinfunction "B_2") (pintype "passive"))
    )
    (net (code "270") (name "unconnected-(C40-Pad3)") (class "Default")
      (node (ref "C40") (pin "3") (pinfunction "3_3") (pintype "passive"))
    )
    (net (code "271") (name "unconnected-(C40-Pad4)") (class "Default")
      (node (ref "C40") (pin "4") (pinfunction "4_4") (pintype "passive"))
    )
    (net (code "272") (name "unconnected-(C40-Pad5)") (class "Default")
      (node (ref "C40") (pin "5") (pinfunction "5_5") (pintype "passive"))
    )
    (net (code "273") (name "unconnected-(C40-Pad6)") (class "Default")
      (node (ref "C40") (pin "6") (pinfunction "6_6") (pintype "passive"))
    )
    (net (code "274") (name "unconnected-(C40-Pad7)") (class "Default")
      (node (ref "C40") (pin "7") (pinfunction "7_7") (pintype "passive"))
    )
    (net (code "275") (name "unconnected-(C40-Pad8)") (class "Default")
      (node (ref "C40") (pin "8") (pinfunction "8_8") (pintype "passive"))
    )
    (net (code "276") (name "unconnected-(C40-Pad13)") (class "Default")
      (node (ref "C40") (pin "13") (pinfunction "13_13") (pintype "passive"))
    )
    (net (code "277") (name "unconnected-(C40-Pad14)") (class "Default")
      (node (ref "C40") (pin "14") (pinfunction "14_14") (pintype "passive"))
    )
    (net (code "278") (name "unconnected-(C40-Pad15)") (class "Default")
      (node (ref "C40") (pin "15") (pinfunction "15_15") (pintype "passive"))
    )
    (net (code "279") (name "unconnected-(C40-Pad16)") (class "Default")
      (node (ref "C40") (pin "16") (pinfunction "16_16") (pintype "passive"))
    )
    (net (code "280") (name "unconnected-(C40-Pad21)") (class "Default")
      (node (ref "C40") (pin "21") (pinfunction "21_21") (pintype "passive"))
    )
    (net (code "281") (name "unconnected-(C40-Pad22)") (class "Default")
      (node (ref "C40") (pin "22") (pinfunction "22_22") (pintype "passive"))
    )
    (net (code "282") (name "unconnected-(C40-Pad26)") (class "Default")
      (node (ref "C40") (pin "26") (pinfunction "26_26") (pintype "passive"))
    )
    (net (code "283") (name "unconnected-(C40-Pad27)") (class "Default")
      (node (ref "C40") (pin "27") (pinfunction "27_27") (pintype "passive"))
    )
    (net (code "284") (name "unconnected-(C40-Pad29)") (class "Default")
      (node (ref "C40") (pin "29") (pinfunction "29_29") (pintype "passive"))
    )
    (net (code "285") (name "unconnected-(C40-Pad30)") (class "Default")
      (node (ref "C40") (pin "30") (pinfunction "30_30") (pintype "passive"))
    )
    (net (code "286") (name "unconnected-(C40-Pad31)") (class "Default")
      (node (ref "C40") (pin "31") (pinfunction "31_31") (pintype "passive"))
    )
    (net (code "287") (name "unconnected-(C40-Pad32)") (class "Default")
      (node (ref "C40") (pin "32") (pinfunction "32_32") (pintype "passive"))
    )
    (net (code "288") (name "unconnected-(D40-Pad1)") (class "Default")
      (node (ref "D40") (pin "1") (pinfunction "1_1") (pintype "passive"))
    )
    (net (code "289") (name "unconnected-(D40-Pad3)") (class "Default")
      (node (ref "D40") (pin "3") (pinfunction "3_3") (pintype "passive"))
    )
    (net (code "290") (name "unconnected-(D40-Pad5)") (class "Default")
      (node (ref "D40") (pin "5") (pinfunction "5_5") (pintype "passive"))
    )
    (net (code "291") (name "unconnected-(D40-Pad7)") (class "Default")
      (node (ref "D40") (pin "7") (pinfunction "7_7") (pintype "passive"))
    )
    (net (code "292") (name "unconnected-(D40-Pad9)") (class "Default")
      (node (ref "D40") (pin "9") (pinfunction "9_9") (pintype "passive"))
    )
    (net (code "293") (name "unconnected-(D40-Pad11)") (class "Default")
      (node (ref "D40") (pin "11") (pinfunction "11_11") (pintype "passive"))
    )
    (net (code "294") (name "unconnected-(D40-Pad13)") (class "Default")
      (node (ref "D40") (pin "13") (pinfunction "13_13") (pintype "passive"))
    )
    (net (code "295") (name "unconnected-(D40-Pad14)") (class "Default")
      (node (ref "D40") (pin "14") (pinfunction "14_14") (pintype "passive"))
    )
    (net (code "296") (name "unconnected-(D40-Pad15)") (class "Default")
      (node (ref "D40") (pin "15") (pinfunction "15_15") (pintype "passive"))
    )
    (net (code "297") (name "unconnected-(D40-Pad21)") (class "Default")
      (node (ref "D40") (pin "21") (pinfunction "21_21") (pintype "passive"))
    )
    (net (code "298") (name "unconnected-(D40-Pad25)") (class "Default")
      (node (ref "D40") (pin "25") (pinfunction "25_25") (pintype "passive"))
    )
    (net (code "299") (name "unconnected-(D40-Pad27)") (class "Default")
      (node (ref "D40") (pin "27") (pinfunction "27_27") (pintype "passive"))
    )
    (net (code "300") (name "unconnected-(D40-Pad29)") (class "Default")
      (node (ref "D40") (pin "29") (pinfunction "29_29") (pintype "passive"))
    )
  )
)
